# -V6.net
KiCad netlist of a schematic drawn in Altium Designer
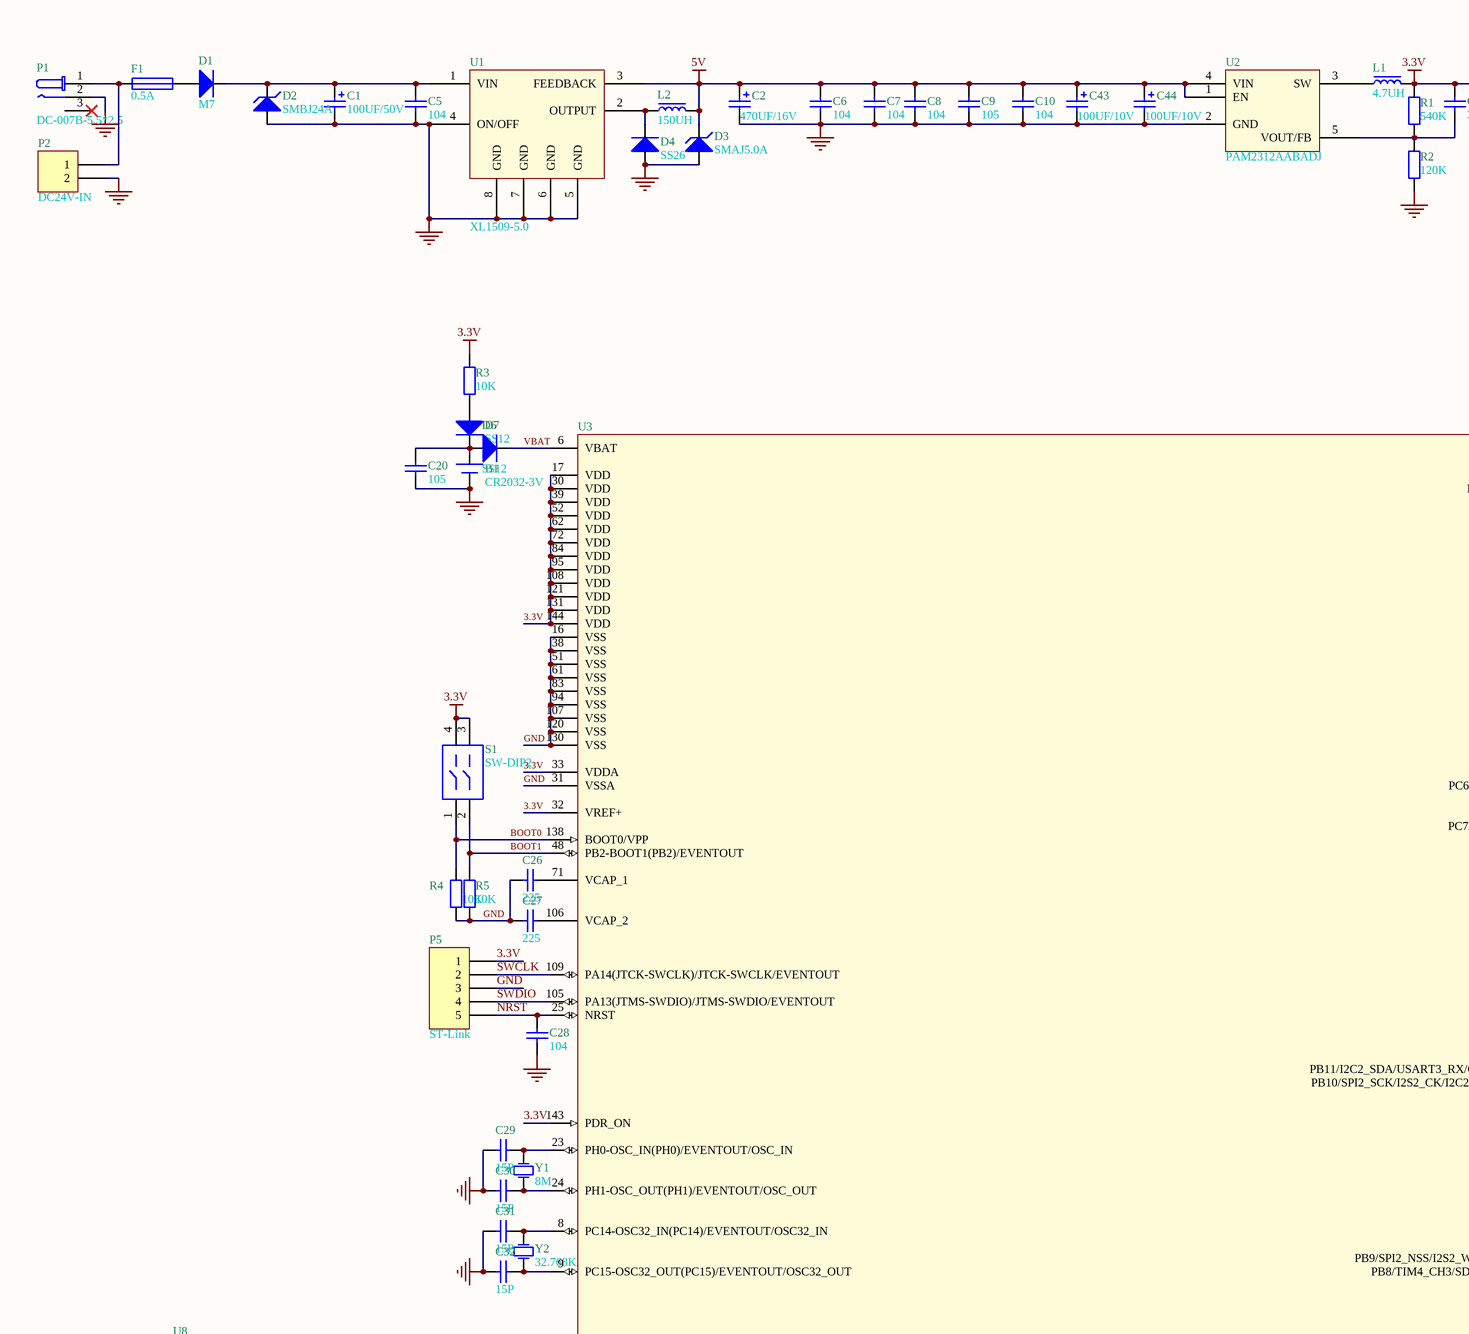
[diagram p0: 通讯转换模块-V6.SchDoc, top left]
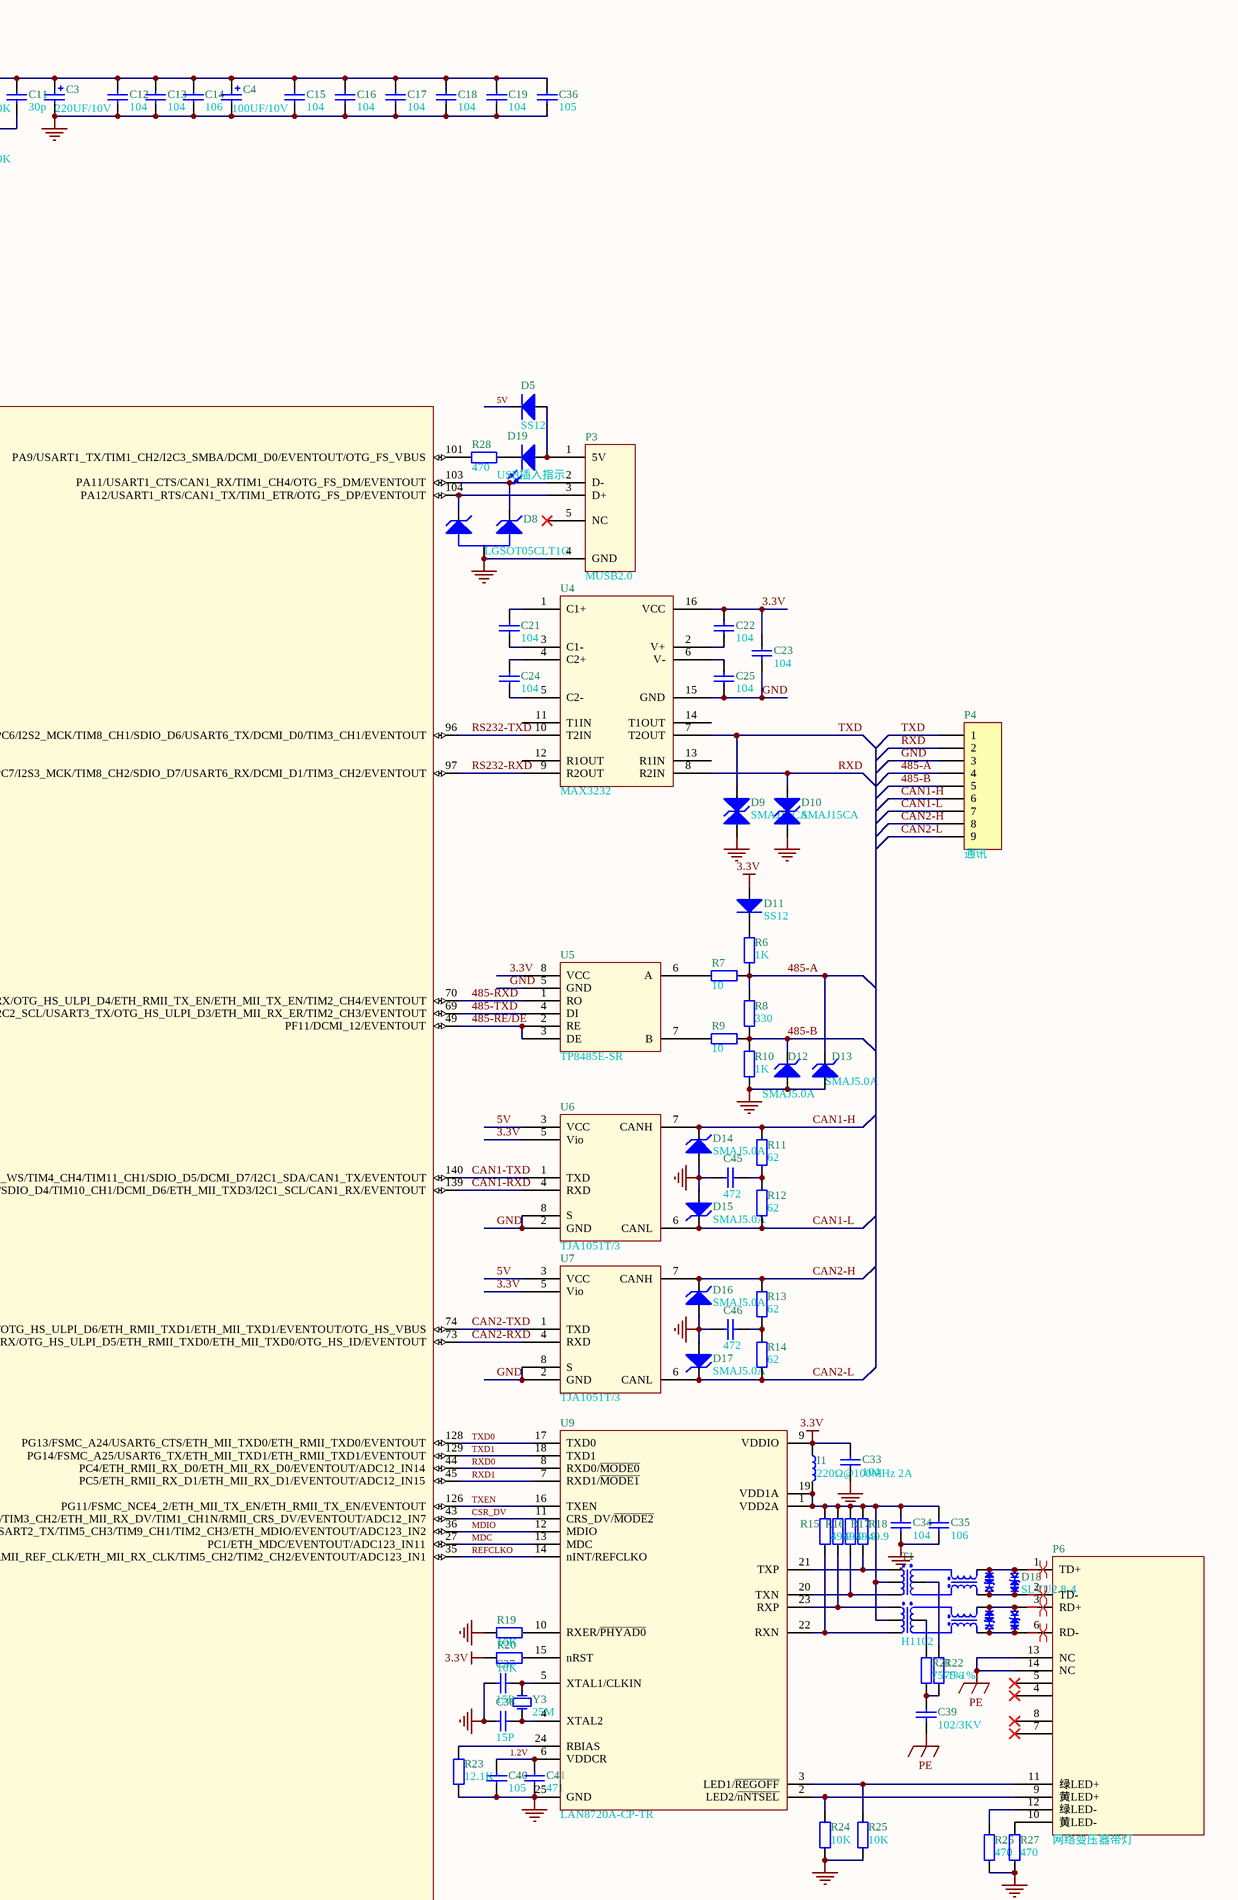
[diagram p1: 通讯转换模块-V6.SchDoc, top right]
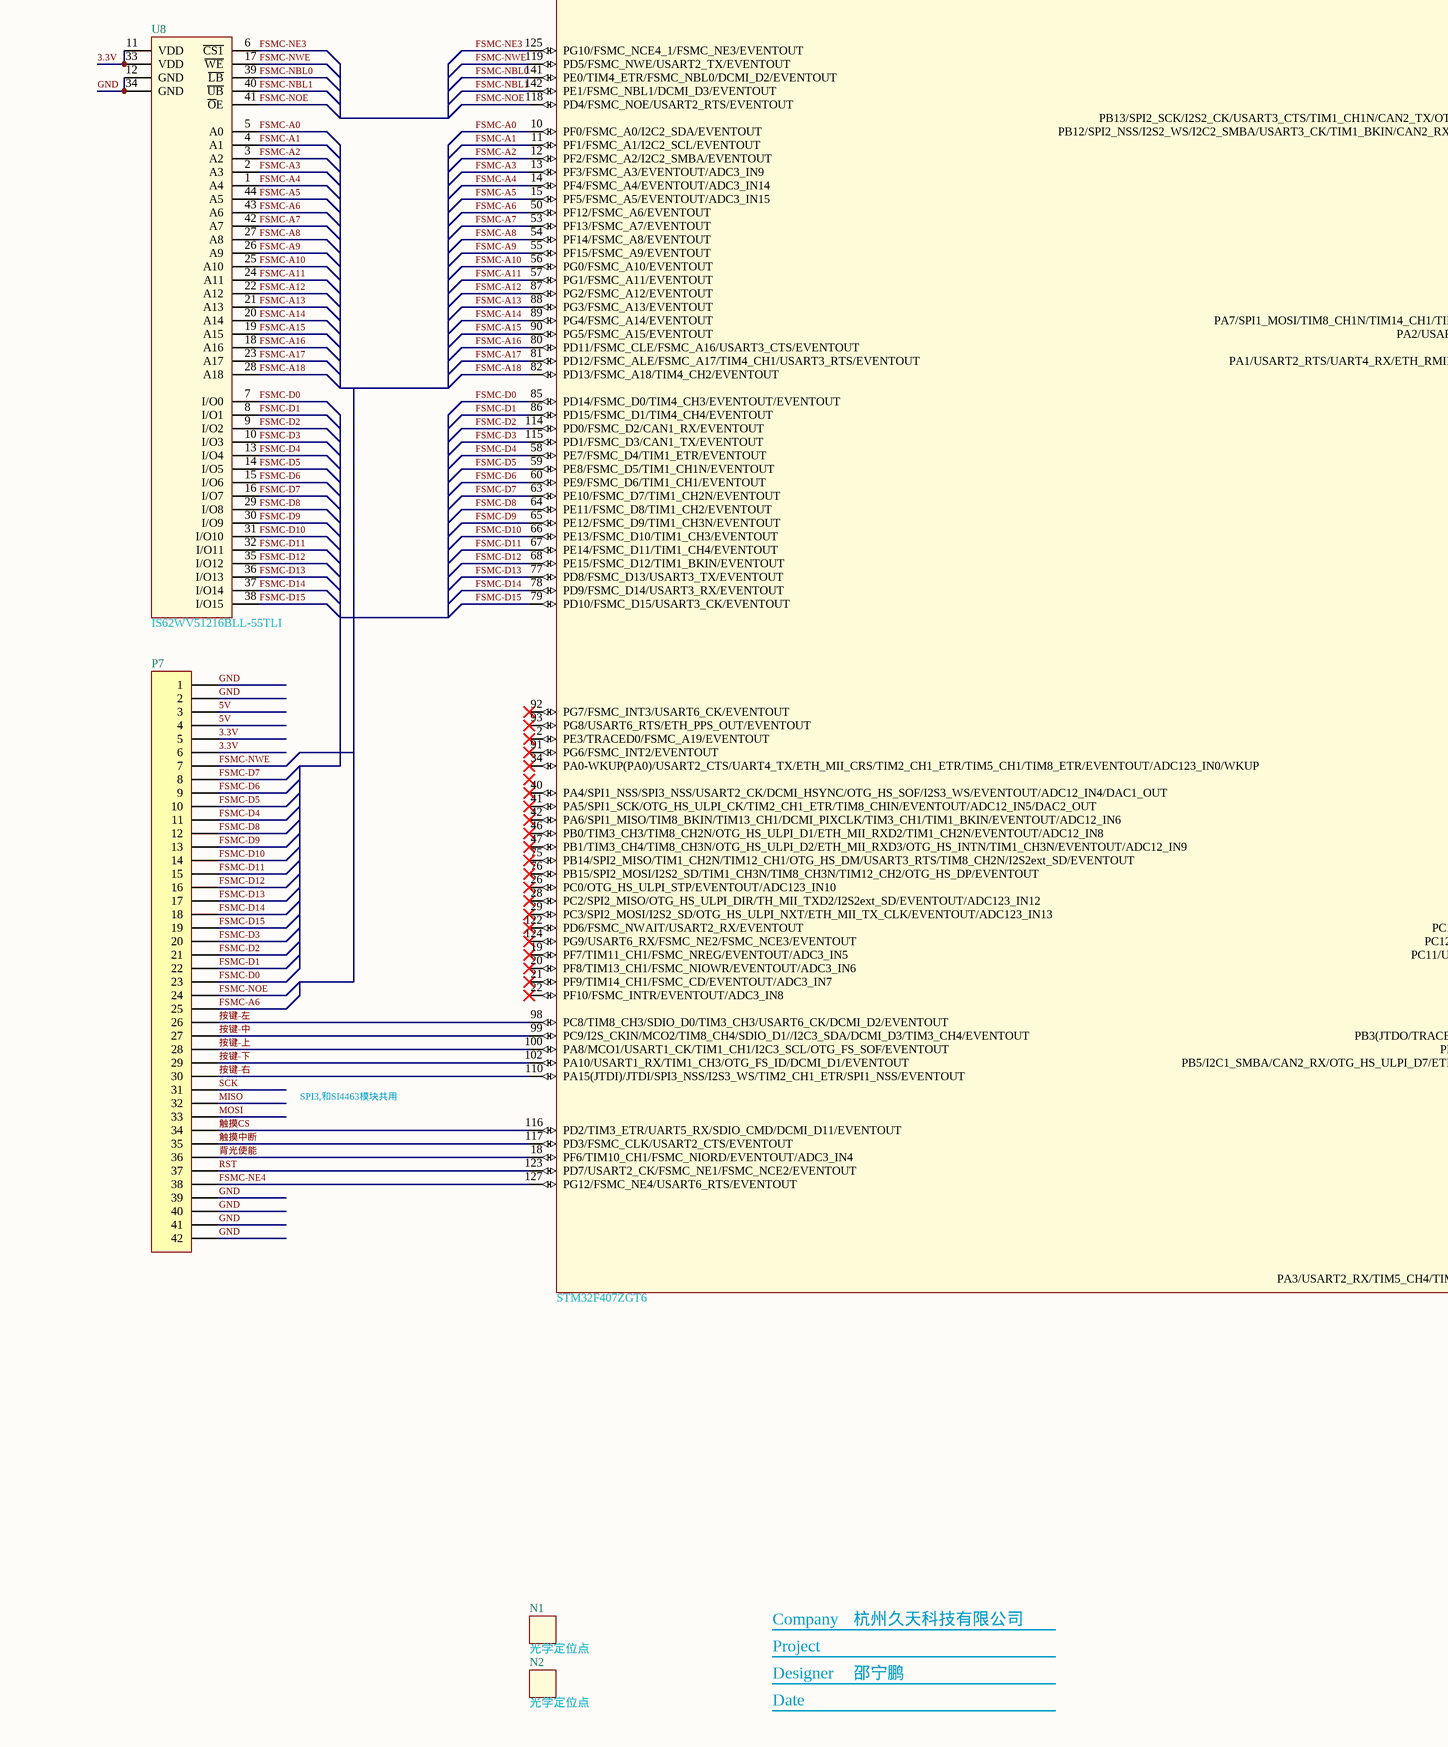
[diagram p2: 通讯转换模块-V6.SchDoc, bottom left]
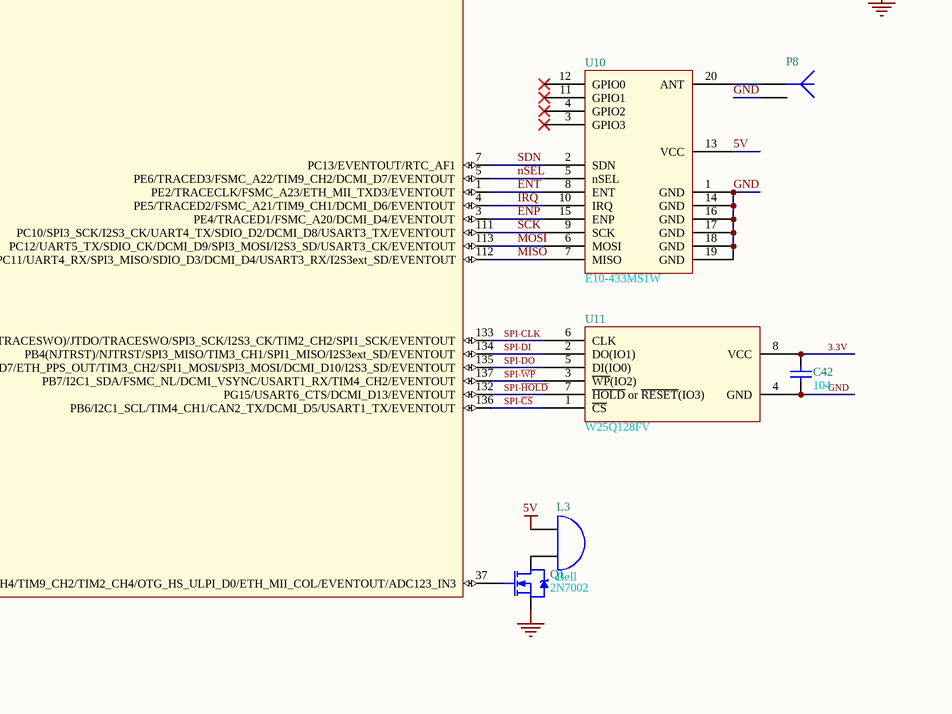
[diagram p3: 通讯转换模块-V6.SchDoc, bottom right]

(export (version "E")
  (design (tool "Eeschema 10.0.6"))
  (components
    (comp (ref "B1")
      (value "CR2032-3V")
      (footprint "CR2032电池座-立式")
      (description "锂电池")
      (libsource (lib "11其他元件-V1.0") (part "Battery1"))
    )
    (comp (ref "C1")
      (value "100UF/50V")
      (footprint "贴片固态电容8*10")
      (description "电解电容")
      (fields (field (name "PUBLISHER") "Altium Limited"))
      (libsource (lib "2电容-V1.0") (part "Cap Pol1"))
    )
    (comp (ref "C2")
      (value "470UF/16V")
      (footprint "贴片固态电容8*10")
      (description "电解电容")
      (fields (field (name "PUBLISHER") "Altium Limited"))
      (libsource (lib "2电容-V1.0") (part "Cap Pol1"))
    )
    (comp (ref "C3")
      (value "220UF/10V")
      (footprint "贴片固态电容6.3*7.7")
      (description "电解电容")
      (fields (field (name "PUBLISHER") "Altium Limited"))
      (libsource (lib "2电容-V1.0") (part "Cap Pol1"))
    )
    (comp (ref "C4")
      (value "100UF/10V")
      (footprint "贴片固态电容5*5.3")
      (description "电解电容")
      (fields (field (name "PUBLISHER") "Altium Limited"))
      (libsource (lib "2电容-V1.0") (part "Cap Pol1"))
    )
    (comp (ref "C5")
      (value "104")
      (footprint "C-0603")
      (description "0805")
      (fields (field (name "PUBLISHER") "Altium Limited"))
      (libsource (lib "2电容-V1.0") (part "Cap-0805"))
    )
    (comp (ref "C6")
      (value "104")
      (footprint "C-0603")
      (description "0805")
      (fields (field (name "PUBLISHER") "Altium Limited"))
      (libsource (lib "2电容-V1.0") (part "Cap-0805"))
    )
    (comp (ref "C7")
      (value "104")
      (footprint "C-0603")
      (description "0805")
      (fields (field (name "PUBLISHER") "Altium Limited"))
      (libsource (lib "2电容-V1.0") (part "Cap-0805"))
    )
    (comp (ref "C8")
      (value "104")
      (footprint "C-0603")
      (description "0805")
      (fields (field (name "PUBLISHER") "Altium Limited"))
      (libsource (lib "2电容-V1.0") (part "Cap-0805"))
    )
    (comp (ref "C9")
      (value "105")
      (footprint "C-0603")
      (description "0805")
      (fields (field (name "PUBLISHER") "Altium Limited"))
      (libsource (lib "2电容-V1.0") (part "Cap-0805"))
    )
    (comp (ref "C10")
      (value "104")
      (footprint "C-0603")
      (description "0805")
      (fields (field (name "PUBLISHER") "Altium Limited"))
      (libsource (lib "2电容-V1.0") (part "Cap-0805"))
    )
    (comp (ref "C11")
      (value "30p")
      (footprint "C-0603")
      (description "0805")
      (fields (field (name "PUBLISHER") "Altium Limited"))
      (libsource (lib "2电容-V1.0") (part "Cap-0805"))
    )
    (comp (ref "C12")
      (value "104")
      (footprint "C-0603")
      (description "0805")
      (fields (field (name "PUBLISHER") "Altium Limited"))
      (libsource (lib "2电容-V1.0") (part "Cap-0805"))
    )
    (comp (ref "C13")
      (value "104")
      (footprint "C-0603")
      (description "0805")
      (fields (field (name "PUBLISHER") "Altium Limited"))
      (libsource (lib "2电容-V1.0") (part "Cap-0805"))
    )
    (comp (ref "C14")
      (value "106")
      (footprint "C-0603")
      (description "0805")
      (fields (field (name "PUBLISHER") "Altium Limited"))
      (libsource (lib "2电容-V1.0") (part "Cap-0805"))
    )
    (comp (ref "C15")
      (value "104")
      (footprint "C-0603")
      (description "0805")
      (fields (field (name "PUBLISHER") "Altium Limited"))
      (libsource (lib "2电容-V1.0") (part "Cap-0805"))
    )
    (comp (ref "C16")
      (value "104")
      (footprint "C-0603")
      (description "0805")
      (fields (field (name "PUBLISHER") "Altium Limited"))
      (libsource (lib "2电容-V1.0") (part "Cap-0805"))
    )
    (comp (ref "C17")
      (value "104")
      (footprint "C-0603")
      (description "0805")
      (fields (field (name "PUBLISHER") "Altium Limited"))
      (libsource (lib "2电容-V1.0") (part "Cap-0805"))
    )
    (comp (ref "C18")
      (value "104")
      (footprint "C-0603")
      (description "0805")
      (fields (field (name "PUBLISHER") "Altium Limited"))
      (libsource (lib "2电容-V1.0") (part "Cap-0805"))
    )
    (comp (ref "C19")
      (value "104")
      (footprint "C-0603")
      (description "0805")
      (fields (field (name "PUBLISHER") "Altium Limited"))
      (libsource (lib "2电容-V1.0") (part "Cap-0805"))
    )
    (comp (ref "C20")
      (value "105")
      (footprint "C-0603")
      (description "0805")
      (fields (field (name "PUBLISHER") "Altium Limited"))
      (libsource (lib "2电容-V1.0") (part "Cap-0603"))
    )
    (comp (ref "C21")
      (value "104")
      (footprint "C-0603")
      (description "0805")
      (fields (field (name "PUBLISHER") "Altium Limited"))
      (libsource (lib "2电容-V1.0") (part "Cap-0805"))
    )
    (comp (ref "C22")
      (value "104")
      (footprint "C-0603")
      (description "0805")
      (fields (field (name "PUBLISHER") "Altium Limited"))
      (libsource (lib "2电容-V1.0") (part "Cap-0805"))
    )
    (comp (ref "C23")
      (value "104")
      (footprint "C-0603")
      (description "0805")
      (fields (field (name "PUBLISHER") "Altium Limited"))
      (libsource (lib "2电容-V1.0") (part "Cap-0805"))
    )
    (comp (ref "C24")
      (value "104")
      (footprint "C-0603")
      (description "0805")
      (fields (field (name "PUBLISHER") "Altium Limited"))
      (libsource (lib "2电容-V1.0") (part "Cap-0805"))
    )
    (comp (ref "C25")
      (value "104")
      (footprint "C-0603")
      (description "0805")
      (fields (field (name "PUBLISHER") "Altium Limited"))
      (libsource (lib "2电容-V1.0") (part "Cap-0805"))
    )
    (comp (ref "C26")
      (value "225")
      (footprint "C-0603")
      (description "0805")
      (fields (field (name "PUBLISHER") "Altium Limited"))
      (libsource (lib "2电容-V1.0") (part "Cap-0603"))
    )
    (comp (ref "C27")
      (value "225")
      (footprint "C-0603")
      (description "0805")
      (fields (field (name "PUBLISHER") "Altium Limited"))
      (libsource (lib "2电容-V1.0") (part "Cap-0603"))
    )
    (comp (ref "C28")
      (value "104")
      (footprint "C-0603")
      (description "0805")
      (fields (field (name "PUBLISHER") "Altium Limited"))
      (libsource (lib "2电容-V1.0") (part "Cap-0603"))
    )
    (comp (ref "C29")
      (value "15P")
      (footprint "C-0603")
      (description "0805")
      (fields (field (name "PUBLISHER") "Altium Limited"))
      (libsource (lib "2电容-V1.0") (part "Cap-0603"))
    )
    (comp (ref "C30")
      (value "15P")
      (footprint "C-0603")
      (description "0805")
      (fields (field (name "PUBLISHER") "Altium Limited"))
      (libsource (lib "2电容-V1.0") (part "Cap-0603"))
    )
    (comp (ref "C31")
      (value "15P")
      (footprint "C-0603")
      (description "0805")
      (fields (field (name "PUBLISHER") "Altium Limited"))
      (libsource (lib "2电容-V1.0") (part "Cap-0603"))
    )
    (comp (ref "C32")
      (value "15P")
      (footprint "C-0603")
      (description "0805")
      (fields (field (name "PUBLISHER") "Altium Limited"))
      (libsource (lib "2电容-V1.0") (part "Cap-0603"))
    )
    (comp (ref "C33")
      (value "104")
      (footprint "C-0603")
      (description "0805")
      (fields (field (name "PUBLISHER") "Altium Limited"))
      (libsource (lib "2电容-V1.0") (part "Cap-0603"))
    )
    (comp (ref "C34")
      (value "104")
      (footprint "C-0603")
      (description "0805")
      (fields (field (name "PUBLISHER") "Altium Limited"))
      (libsource (lib "2电容-V1.0") (part "Cap-0603"))
    )
    (comp (ref "C35")
      (value "106")
      (footprint "C-0603")
      (description "0805")
      (fields (field (name "PUBLISHER") "Altium Limited"))
      (libsource (lib "2电容-V1.0") (part "Cap-0603"))
    )
    (comp (ref "C36")
      (value "105")
      (footprint "C-0603")
      (description "0805")
      (fields (field (name "PUBLISHER") "Altium Limited"))
      (libsource (lib "2电容-V1.0") (part "Cap-0603"))
    )
    (comp (ref "C37")
      (value "15P")
      (footprint "C-0603")
      (description "0805")
      (fields (field (name "PUBLISHER") "Altium Limited"))
      (libsource (lib "2电容-V1.0") (part "Cap-0603"))
    )
    (comp (ref "C38")
      (value "15P")
      (footprint "C-0603")
      (description "0805")
      (fields (field (name "PUBLISHER") "Altium Limited"))
      (libsource (lib "2电容-V1.0") (part "Cap-0603"))
    )
    (comp (ref "C39")
      (value "102/3KV")
      (footprint "C-1206")
      (description "0805")
      (fields (field (name "PUBLISHER") "Altium Limited"))
      (libsource (lib "2电容-V1.0") (part "Cap-0805"))
    )
    (comp (ref "C40")
      (value "105")
      (footprint "C-0603")
      (description "0805")
      (fields (field (name "PUBLISHER") "Altium Limited"))
      (libsource (lib "2电容-V1.0") (part "Cap-0603"))
    )
    (comp (ref "C41")
      (value "471")
      (footprint "C-0603")
      (description "0805")
      (fields (field (name "PUBLISHER") "Altium Limited"))
      (libsource (lib "2电容-V1.0") (part "Cap-0603"))
    )
    (comp (ref "C42")
      (value "104")
      (footprint "C-0603")
      (description "0805")
      (fields (field (name "PUBLISHER") "Altium Limited"))
      (libsource (lib "2电容-V1.0") (part "Cap-0603"))
    )
    (comp (ref "C43")
      (value "100UF/10V")
      (footprint "贴片固态电容5*5.3")
      (description "电解电容")
      (fields (field (name "PUBLISHER") "Altium Limited"))
      (libsource (lib "2电容-V1.0") (part "Cap Pol1"))
    )
    (comp (ref "C44")
      (value "100UF/10V")
      (footprint "贴片固态电容5*5.3")
      (description "电解电容")
      (fields (field (name "PUBLISHER") "Altium Limited"))
      (libsource (lib "2电容-V1.0") (part "Cap Pol1"))
    )
    (comp (ref "C45")
      (value "472")
      (footprint "C-0603")
      (description "0805")
      (fields (field (name "PUBLISHER") "Altium Limited"))
      (libsource (lib "2电容-V1.0") (part "Cap-0603"))
    )
    (comp (ref "C46")
      (value "472")
      (footprint "C-0603")
      (description "0805")
      (fields (field (name "PUBLISHER") "Altium Limited"))
      (libsource (lib "2电容-V1.0") (part "Cap-0603"))
    )
    (comp (ref "D1")
      (value "M7")
      (footprint "SMA")
      (description "SMA")
      (fields (field (name "PUBLISHER") "Altium Limited"))
      (libsource (lib "4二极管-V1.1") (part "M7"))
    )
    (comp (ref "D2")
      (value "SMBJ24A")
      (footprint "SMB")
      (description "SMB")
      (libsource (lib "4二极管-V1.1") (part "TVS-1"))
    )
    (comp (ref "D3")
      (value "SMAJ5.0A")
      (footprint "SMA")
      (description "SMB")
      (libsource (lib "4二极管-V1.1") (part "TVS-1"))
    )
    (comp (ref "D4")
      (value "SS26")
      (footprint "SMA")
      (description "SMA")
      (libsource (lib "4二极管-V1.1") (part "SS14"))
    )
    (comp (ref "D5")
      (value "SS12")
      (footprint "D-1206")
      (description "SMA")
      (libsource (lib "4二极管-V1.1") (part "SS14"))
    )
    (comp (ref "D6")
      (value "SS12")
      (footprint "D-1206")
      (description "SMA")
      (libsource (lib "4二极管-V1.1") (part "SS14"))
    )
    (comp (ref "D7")
      (value "SS12")
      (footprint "D-1206")
      (description "SMA")
      (libsource (lib "4二极管-V1.1") (part "SS14"))
    )
    (comp (ref "D8")
      (value "LGSOT05CLT1G")
      (footprint "SOT-23")
      (description "ESD")
      (libsource (lib "4二极管-V1.1") (part "ESDA5V3L"))
    )
    (comp (ref "D9")
      (value "SMAJ15CA")
      (footprint "SMA无极性")
      (description "SMB")
      (libsource (lib "4二极管-V1.1") (part "TVS-2"))
    )
    (comp (ref "D10")
      (value "SMAJ15CA")
      (footprint "SMA无极性")
      (description "SMB")
      (libsource (lib "4二极管-V1.1") (part "TVS-2"))
    )
    (comp (ref "D11")
      (value "SS12")
      (footprint "D-1206")
      (description "SMA")
      (libsource (lib "4二极管-V1.1") (part "SS14"))
    )
    (comp (ref "D12")
      (value "SMAJ5.0A")
      (footprint "SMA")
      (description "SMB")
      (libsource (lib "4二极管-V1.1") (part "TVS-1"))
    )
    (comp (ref "D13")
      (value "SMAJ5.0A")
      (footprint "SMA")
      (description "SMB")
      (libsource (lib "4二极管-V1.1") (part "TVS-1"))
    )
    (comp (ref "D14")
      (value "SMAJ5.0A")
      (footprint "SMA")
      (description "SMB")
      (libsource (lib "4二极管-V1.1") (part "TVS-1"))
    )
    (comp (ref "D15")
      (value "SMAJ5.0A")
      (footprint "SMA")
      (description "SMB")
      (libsource (lib "4二极管-V1.1") (part "TVS-1"))
    )
    (comp (ref "D16")
      (value "SMAJ5.0A")
      (footprint "SMA")
      (description "SMB")
      (libsource (lib "4二极管-V1.1") (part "TVS-1"))
    )
    (comp (ref "D17")
      (value "SMAJ5.0A")
      (footprint "SMA")
      (description "SMB")
      (libsource (lib "4二极管-V1.1") (part "TVS-1"))
    )
    (comp (ref "D18")
      (value "SLVU2.8-4")
      (footprint "SOP-8-N")
      (libsource (lib "4二极管-V1.1") (part "SLVU2.8-4"))
    )
    (comp (ref "D19")
      (value "USB插入指示")
      (footprint "LED-0603-Red")
      (fields (field (name "PUBLISHER") "Altium Limited"))
      (libsource (lib "4二极管-V1.1") (part "LED-0603-Blue"))
    )
    (comp (ref "F1")
      (value "0.5A")
      (footprint "FUSE-1808")
      (description "Fuse")
      (fields (field (name "PUBLISHER") "Altium Limited"))
      (libsource (lib "11其他元件-V1.0") (part "Fuse 1"))
    )
    (comp (ref "I1")
      (value "220Ω@100MHz 2A")
      (footprint "L-0805")
      (libsource (lib "3电感-V1.0") (part "Inductance1"))
    )
    (comp (ref "L1") (value "4.7UH") (footprint "CD54") (libsource (lib "3电感-V1.0") (part "Inductance3")))
    (comp (ref "L2") (value "150UH") (footprint "CD75") (libsource (lib "3电感-V1.0") (part "Inductance3")))
    (comp (ref "L3")
      (value "Bell")
      (footprint "蜂鸣器 YH-8503-A")
      (description "Electrical Bell")
      (fields (field (name "PUBLISHER") "Altium Limited"))
      (libsource (lib "11其他元件-V1.0") (part "Bell"))
    )
    (comp (ref "N1") (value "光学定位点") (footprint "MARK-1mm-3mm") (libsource (lib "11其他元件-V1.0") (part "无引脚")))
    (comp (ref "N2") (value "光学定位点") (footprint "MARK-1mm-3mm") (libsource (lib "11其他元件-V1.0") (part "无引脚")))
    (comp (ref "P1")
      (value "DC-007B-5.5*2.5")
      (footprint "DC-007B")
      (libsource (lib "PJ系列") (part "DC-007B"))
    )
    (comp (ref "P2")
      (value "DC24V-IN")
      (footprint "KF2EDG5.08V-2P-有挡边-卧式")
      (description "Header, 2-Pin")
      (fields (field (name "PUBLISHER") "Altium Limited"))
      (libsource (lib "5排针-V1.0") (part "Header 2"))
    )
    (comp (ref "P3")
      (value "MUSB2.0")
      (footprint "USB1.1-插件-母座")
      (libsource (lib "11其他元件-V1.0") (part "USB-4_A"))
    )
    (comp (ref "P4")
      (value "通讯")
      (footprint "KF2EDG5.08V-9P-有挡边-卧式")
      (description "Header, 9-Pin")
      (fields (field (name "PUBLISHER") "Altium Limited"))
      (libsource (lib "5排针-V1.0") (part "Header 9"))
    )
    (comp (ref "P5")
      (value "ST-Link")
      (footprint "HDR1X5")
      (description "Header, 5-Pin")
      (fields (field (name "PUBLISHER") "Altium Limited"))
      (libsource (lib "5排针-V1.0") (part "Header 5"))
    )
    (comp (ref "P6")
      (value "网络变压器带灯")
      (footprint "RJ45-8P8C-56带灯")
      (libsource (lib "11其他元件-V1.0") (part "网络变压器带灯"))
    )
    (comp (ref "P7")
      (value "~")
      (footprint "FPC-0.5mm_40P下接翻盖")
      (libsource (lib "5排针-V1.0") (part "MHDR1X42"))
    )
    (comp (ref "P8") (value "SMA-KWE") (footprint "SMA-KWE") (libsource (lib "11其他元件-V1.0") (part "天线座")))
    (comp (ref "Q1") (value "2N7002") (footprint "SOT-23") (libsource (lib "4二极管-V1.1") (part "2N7002")))
    (comp (ref "R1")
      (value "540K")
      (footprint "R-0603")
      (description "0603")
      (fields (field (name "PUBLISHER") "Altium Limited"))
      (libsource (lib "") (part "Res2-0603_1"))
    )
    (comp (ref "R2")
      (value "120K")
      (footprint "R-0603")
      (description "0603")
      (fields (field (name "PUBLISHER") "Altium Limited"))
      (libsource (lib "") (part "Res2-0603_1"))
    )
    (comp (ref "R3")
      (value "10K")
      (footprint "R-0603")
      (description "0603")
      (fields (field (name "PUBLISHER") "Altium Limited"))
      (libsource (lib "") (part "Res2-0603_1"))
    )
    (comp (ref "R4")
      (value "10K")
      (footprint "R-0603")
      (description "0603")
      (fields (field (name "PUBLISHER") "Altium Limited"))
      (libsource (lib "") (part "Res2-0603_1"))
    )
    (comp (ref "R5")
      (value "10K")
      (footprint "R-0603")
      (description "0603")
      (fields (field (name "PUBLISHER") "Altium Limited"))
      (libsource (lib "") (part "Res2-0603_1"))
    )
    (comp (ref "R6")
      (value "1K")
      (footprint "R-0603")
      (description "Resistor")
      (fields (field (name "PUBLISHER") "Altium Limited"))
      (libsource (lib "") (part "Res2_1"))
    )
    (comp (ref "R7")
      (value "10")
      (footprint "R-0805")
      (description "Resistor")
      (fields (field (name "PUBLISHER") "Altium Limited"))
      (libsource (lib "") (part "Res2_1"))
    )
    (comp (ref "R8")
      (value "330")
      (footprint "R-1206")
      (description "Resistor")
      (fields (field (name "PUBLISHER") "Altium Limited"))
      (libsource (lib "Miscellaneous Devices") (part "Res2"))
    )
    (comp (ref "R9")
      (value "10")
      (footprint "R-0805")
      (description "Resistor")
      (fields (field (name "PUBLISHER") "Altium Limited"))
      (libsource (lib "") (part "Res2_1"))
    )
    (comp (ref "R10")
      (value "1K")
      (footprint "R-0603")
      (description "Resistor")
      (fields (field (name "PUBLISHER") "Altium Limited"))
      (libsource (lib "元件2.0") (part "Res2"))
    )
    (comp (ref "R11")
      (value "62")
      (footprint "R-1206")
      (description "Resistor")
      (fields (field (name "PUBLISHER") "Altium Limited"))
      (libsource (lib "Miscellaneous Devices") (part "Res2"))
    )
    (comp (ref "R12")
      (value "62")
      (footprint "R-1206")
      (description "Resistor")
      (fields (field (name "PUBLISHER") "Altium Limited"))
      (libsource (lib "Miscellaneous Devices") (part "Res2"))
    )
    (comp (ref "R13")
      (value "62")
      (footprint "R-1206")
      (description "Resistor")
      (fields (field (name "PUBLISHER") "Altium Limited"))
      (libsource (lib "Miscellaneous Devices") (part "Res2"))
    )
    (comp (ref "R14")
      (value "62")
      (footprint "R-1206")
      (description "Resistor")
      (fields (field (name "PUBLISHER") "Altium Limited"))
      (libsource (lib "Miscellaneous Devices") (part "Res2"))
    )
    (comp (ref "R15")
      (value "49.9")
      (footprint "R-0603")
      (description "Resistor")
      (fields (field (name "PUBLISHER") "Altium Limited"))
      (libsource (lib "元件2.0") (part "Res2"))
    )
    (comp (ref "R16")
      (value "49.9")
      (footprint "R-0603")
      (description "Resistor")
      (fields (field (name "PUBLISHER") "Altium Limited"))
      (libsource (lib "元件2.0") (part "Res2"))
    )
    (comp (ref "R17")
      (value "49.9")
      (footprint "R-0603")
      (description "Resistor")
      (fields (field (name "PUBLISHER") "Altium Limited"))
      (libsource (lib "元件2.0") (part "Res2"))
    )
    (comp (ref "R18")
      (value "49.9")
      (footprint "R-0603")
      (description "Resistor")
      (fields (field (name "PUBLISHER") "Altium Limited"))
      (libsource (lib "元件2.0") (part "Res2"))
    )
    (comp (ref "R19")
      (value "10K")
      (footprint "R-0603")
      (description "0603")
      (fields (field (name "PUBLISHER") "Altium Limited"))
      (libsource (lib "") (part "Res2-0603_2"))
    )
    (comp (ref "R20")
      (value "10K")
      (footprint "R-0603")
      (description "0603")
      (fields (field (name "PUBLISHER") "Altium Limited"))
      (libsource (lib "") (part "Res2-0603_2"))
    )
    (comp (ref "R21")
      (value "75-1%")
      (footprint "R-0603")
      (description "0805")
      (fields (field (name "PUBLISHER") "Altium Limited"))
      (libsource (lib "1电阻-V1.0") (part "Res2-0805"))
    )
    (comp (ref "R22")
      (value "75-1%")
      (footprint "R-0603")
      (description "0805")
      (fields (field (name "PUBLISHER") "Altium Limited"))
      (libsource (lib "") (part "Res2-0805_1"))
    )
    (comp (ref "R23")
      (value "12.1K")
      (footprint "R-0603")
      (description "0603")
      (fields (field (name "PUBLISHER") "Altium Limited"))
      (libsource (lib "1电阻-V1.0") (part "Res2-0603"))
    )
    (comp (ref "R24")
      (value "10K")
      (footprint "R-0603")
      (description "0603")
      (fields (field (name "PUBLISHER") "Altium Limited"))
      (libsource (lib "1电阻-V1.0") (part "Res2-0603"))
    )
    (comp (ref "R25")
      (value "10K")
      (footprint "R-0603")
      (description "0603")
      (fields (field (name "PUBLISHER") "Altium Limited"))
      (libsource (lib "1电阻-V1.0") (part "Res2-0603"))
    )
    (comp (ref "R26")
      (value "470")
      (footprint "R-0603")
      (description "0603")
      (fields (field (name "PUBLISHER") "Altium Limited"))
      (libsource (lib "") (part "Res2-0603_3"))
    )
    (comp (ref "R27")
      (value "470")
      (footprint "R-0603")
      (description "0603")
      (fields (field (name "PUBLISHER") "Altium Limited"))
      (libsource (lib "1电阻-V1.0") (part "Res2-0603"))
    )
    (comp (ref "R28")
      (value "470")
      (footprint "R-0603")
      (description "0603")
      (fields (field (name "PUBLISHER") "Altium Limited"))
      (libsource (lib "") (part "Res2-0603_2"))
    )
    (comp (ref "S1")
      (value "SW-DIP2")
      (footprint "SW-红色拨码开关2P")
      (fields (field (name "PUBLISHER") "Altium Limited"))
      (libsource (lib "开关-V1") (part "SW-DIP2"))
    )
    (comp (ref "T1") (value "H1102") (footprint "H1102") (libsource (lib "3电感-V1.0") (part "H1102")))
    (comp (ref "U1")
      (value "XL1509-5.0")
      (footprint "SOP-8-N")
      (description "开关电源 SOP-8")
      (libsource (lib "8集成电路-V1.1") (part "XL1509-ADJ"))
    )
    (comp (ref "U2")
      (value "PAM2312AABADJ")
      (footprint "SOT-23-5-M")
      (description "开关电源 SOT-23-5")
      (libsource (lib "电源芯片DC-DC") (part "PAM2312"))
    )
    (comp (ref "U3")
      (value "STM32F407ZGT6")
      (footprint "TQFP-144-L")
      (libsource (lib "9单片机-V1.0") (part "STM32F407ZET6"))
    )
    (comp (ref "U4") (value "MAX3232") (footprint "SOP-16-N") (libsource (lib "8集成电路-V1.1") (part "MAX3232")))
    (comp (ref "U5")
      (value "TP8485E-SR")
      (footprint "SOP-8-N")
      (description "RS485总线转串口")
      (libsource (lib "集成电路1.0") (part "MAX3082"))
    )
    (comp (ref "U6") (value "TJA1051T/3") (footprint "SOP-8-N") (libsource (lib "通讯-V1") (part "TJA1051T/3")))
    (comp (ref "U7") (value "TJA1051T/3") (footprint "SOP-8-N") (libsource (lib "通讯-V1") (part "TJA1051T/3")))
    (comp (ref "U8")
      (value "IS62WV51216BLL-55TLI")
      (footprint "TSOP2-44-L")
      (libsource (lib "存储") (part "IS62WV51216BLL-55TLI"))
    )
    (comp (ref "U9")
      (value "LAN8720A-CP-TR")
      (footprint "QFN-24")
      (description "以太网PHY")
      (libsource (lib "通讯-V1") (part "LAN8720A-CP-TR"))
    )
    (comp (ref "U10")
      (value "E10-433MS1W")
      (footprint "E10-433MS1W")
      (description "433模块")
      (libsource (lib "6电路模块-V1.0") (part "E10-433MS1W"))
    )
    (comp (ref "U11")
      (value "W25Q128FV")
      (footprint "SOIC-8-M")
      (description "SPI-FLASH")
      (libsource (lib "8集成电路-V1.1") (part "W25Q128FV"))
    )
    (comp (ref "Y1") (value "8M") (footprint "HC-49SMD") (libsource (lib "11其他元件-V1.0") (part "晶振")))
    (comp (ref "Y2") (value "32.768K") (footprint "FC135") (libsource (lib "11其他元件-V1.0") (part "晶振")))
    (comp (ref "Y3") (value "25M") (footprint "HC-49SMD") (libsource (lib "11其他元件-V1.0") (part "晶振")))
  )
  (nets
    (net (code "1") (name "/1.2V") (class "Default")
      (node (ref "C40") (pin "2") (pinfunction "2_2") (pintype "passive"))
      (node (ref "C41") (pin "2") (pinfunction "2_2") (pintype "passive"))
      (node (ref "U9") (pin "6") (pinfunction "VDDCR_6") (pintype "passive"))
    )
    (net (code "2") (name "/485-A") (class "Default")
      (node (ref "D13") (pin "2") (pinfunction "K_2") (pintype "passive"))
      (node (ref "P4") (pin "4") (pinfunction "4_4") (pintype "passive"))
      (node (ref "R6") (pin "2") (pinfunction "2_2") (pintype "passive"))
      (node (ref "R7") (pin "1") (pinfunction "1_1") (pintype "passive"))
      (node (ref "R8") (pin "1") (pinfunction "1_1") (pintype "passive"))
    )
    (net (code "3") (name "/485-B") (class "Default")
      (node (ref "D12") (pin "2") (pinfunction "K_2") (pintype "passive"))
      (node (ref "P4") (pin "5") (pinfunction "5_5") (pintype "passive"))
      (node (ref "R10") (pin "2") (pinfunction "2_2") (pintype "passive"))
      (node (ref "R8") (pin "2") (pinfunction "2_2") (pintype "passive"))
      (node (ref "R9") (pin "1") (pinfunction "1_1") (pintype "passive"))
    )
    (net (code "4") (name "/485-RE{slash}DE") (class "Default")
      (node (ref "U3") (pin "49") (pinfunction "PF11/DCMI_12/EVENTOUT_49") (pintype "bidirectional"))
      (node (ref "U5") (pin "2") (pinfunction "RE_2") (pintype "passive"))
      (node (ref "U5") (pin "3") (pinfunction "DE_3") (pintype "passive"))
    )
    (net (code "5") (name "/485-RXD") (class "Default")
      (node (ref "U3") (pin "70") (pinfunction "PB11/I2C2_SDA/USART3_RX/OTG_HS_ULPI_D4/ETH_RMII_TX_EN/ETH_MII_TX_EN/TIM2_CH4/EVENTOUT_70") (pintype "bidirectional"))
      (node (ref "U5") (pin "1") (pinfunction "RO_1") (pintype "passive"))
    )
    (net (code "6") (name "/485-TXD") (class "Default")
      (node (ref "U3") (pin "69") (pinfunction "PB10/SPI2_SCK/I2S2_CK/I2C2_SCL/USART3_TX/OTG_HS_ULPI_D3/ETH_MII_RX_ER/TIM2_CH3/EVENTOUT_69") (pintype "bidirectional"))
      (node (ref "U5") (pin "4") (pinfunction "DI_4") (pintype "passive"))
    )
    (net (code "7") (name "/BOOT0") (class "Default")
      (node (ref "R4") (pin "2") (pinfunction "2_2") (pintype "passive"))
      (node (ref "S1") (pin "1") (pinfunction "1_1") (pintype "passive"))
      (node (ref "U3") (pin "138") (pinfunction "BOOT0/VPP_138") (pintype "input"))
    )
    (net (code "8") (name "/BOOT1") (class "Default")
      (node (ref "R5") (pin "2") (pinfunction "2_2") (pintype "passive"))
      (node (ref "S1") (pin "2") (pinfunction "2_2") (pintype "passive"))
      (node (ref "U3") (pin "48") (pinfunction "PB2-BOOT1(PB2)/EVENTOUT_48") (pintype "bidirectional"))
    )
    (net (code "9") (name "/CAN1-H") (class "Default")
      (node (ref "D14") (pin "2") (pinfunction "K_2") (pintype "passive"))
      (node (ref "P4") (pin "6") (pinfunction "6_6") (pintype "passive"))
      (node (ref "R11") (pin "1") (pinfunction "1_1") (pintype "passive"))
      (node (ref "U6") (pin "7") (pinfunction "CANH_7") (pintype "passive"))
    )
    (net (code "10") (name "/CAN1-L") (class "Default")
      (node (ref "D15") (pin "2") (pinfunction "K_2") (pintype "passive"))
      (node (ref "P4") (pin "7") (pinfunction "7_7") (pintype "passive"))
      (node (ref "R12") (pin "2") (pinfunction "2_2") (pintype "passive"))
      (node (ref "U6") (pin "6") (pinfunction "CANL_6") (pintype "passive"))
    )
    (net (code "11") (name "/CAN1-RXD") (class "Default")
      (node (ref "U3") (pin "139") (pinfunction "PB8/TIM4_CH3/SDIO_D4/TIM10_CH1/DCMI_D6/ETH_MII_TXD3/I2C1_SCL/CAN1_RX/EVENTOUT_139") (pintype "bidirectional"))
      (node (ref "U6") (pin "4") (pinfunction "RXD_4") (pintype "passive"))
    )
    (net (code "12") (name "/CAN1-TXD") (class "Default")
      (node (ref "U3") (pin "140") (pinfunction "PB9/SPI2_NSS/I2S2_WS/TIM4_CH4/TIM11_CH1/SDIO_D5/DCMI_D7/I2C1_SDA/CAN1_TX/EVENTOUT_140") (pintype "bidirectional"))
      (node (ref "U6") (pin "1") (pinfunction "TXD_1") (pintype "passive"))
    )
    (net (code "13") (name "/CAN2-H") (class "Default")
      (node (ref "D16") (pin "2") (pinfunction "K_2") (pintype "passive"))
      (node (ref "P4") (pin "8") (pinfunction "8_8") (pintype "passive"))
      (node (ref "R13") (pin "1") (pinfunction "1_1") (pintype "passive"))
      (node (ref "U7") (pin "7") (pinfunction "CANH_7") (pintype "passive"))
    )
    (net (code "14") (name "/CAN2-L") (class "Default")
      (node (ref "D17") (pin "2") (pinfunction "K_2") (pintype "passive"))
      (node (ref "P4") (pin "9") (pinfunction "9_9") (pintype "passive"))
      (node (ref "R14") (pin "2") (pinfunction "2_2") (pintype "passive"))
      (node (ref "U7") (pin "6") (pinfunction "CANL_6") (pintype "passive"))
    )
    (net (code "15") (name "/CAN2-RXD") (class "Default")
      (node (ref "U3") (pin "73") (pinfunction "PB12/SPI2_NSS/I2S2_WS/I2C2_SMBA/USART3_CK/TIM1_BKIN/CAN2_RX/OTG_HS_ULPI_D5/ETH_RMII_TXD0/ETH_MII_TXD0/OTG_HS_ID/EVENTOUT_73") (pintype "bidirectional"))
      (node (ref "U7") (pin "4") (pinfunction "RXD_4") (pintype "passive"))
    )
    (net (code "16") (name "/CAN2-TXD") (class "Default")
      (node (ref "U3") (pin "74") (pinfunction "PB13/SPI2_SCK/I2S2_CK/USART3_CTS/TIM1_CH1N/CAN2_TX/OTG_HS_ULPI_D6/ETH_RMII_TXD1/ETH_MII_TXD1/EVENTOUT/OTG_HS_VBUS_74") (pintype "bidirectional"))
      (node (ref "U7") (pin "1") (pinfunction "TXD_1") (pintype "passive"))
    )
    (net (code "17") (name "/CSR_DV") (class "Default")
      (node (ref "U3") (pin "43") (pinfunction "PA7/SPI1_MOSI/TIM8_CH1N/TIM14_CH1/TIM3_CH2/ETH_MII_RX_DV/TIM1_CH1N/RMII_CRS_DV/EVENTOUT/ADC12_IN7_43") (pintype "bidirectional"))
      (node (ref "U9") (pin "11") (pinfunction "CRS_DV/~{MODE2}_11") (pintype "passive"))
    )
    (net (code "18") (name "/ENP") (class "Default")
      (node (ref "U10") (pin "15") (pinfunction "ENP_15") (pintype "passive"))
      (node (ref "U3") (pin "3") (pinfunction "PE4/TRACED1/FSMC_A20/DCMI_D4/EVENTOUT_3") (pintype "bidirectional"))
    )
    (net (code "19") (name "/ENT") (class "Default")
      (node (ref "U10") (pin "8") (pinfunction "ENT_8") (pintype "passive"))
      (node (ref "U3") (pin "1") (pinfunction "PE2/TRACECLK/FSMC_A23/ETH_MII_TXD3/EVENTOUT_1") (pintype "bidirectional"))
    )
    (net (code "20") (name "/FSMC-A0") (class "Default")
      (node (ref "U3") (pin "10") (pinfunction "PF0/FSMC_A0/I2C2_SDA/EVENTOUT_10") (pintype "bidirectional"))
      (node (ref "U8") (pin "5") (pinfunction "A0_5") (pintype "passive"))
    )
    (net (code "21") (name "/FSMC-A1") (class "Default")
      (node (ref "U3") (pin "11") (pinfunction "PF1/FSMC_A1/I2C2_SCL/EVENTOUT_11") (pintype "bidirectional"))
      (node (ref "U8") (pin "4") (pinfunction "A1_4") (pintype "passive"))
    )
    (net (code "22") (name "/FSMC-A2") (class "Default")
      (node (ref "U3") (pin "12") (pinfunction "PF2/FSMC_A2/I2C2_SMBA/EVENTOUT_12") (pintype "bidirectional"))
      (node (ref "U8") (pin "3") (pinfunction "A2_3") (pintype "passive"))
    )
    (net (code "23") (name "/FSMC-A3") (class "Default")
      (node (ref "U3") (pin "13") (pinfunction "PF3/FSMC_A3/EVENTOUT/ADC3_IN9_13") (pintype "bidirectional"))
      (node (ref "U8") (pin "2") (pinfunction "A3_2") (pintype "passive"))
    )
    (net (code "24") (name "/FSMC-A4") (class "Default")
      (node (ref "U3") (pin "14") (pinfunction "PF4/FSMC_A4/EVENTOUT/ADC3_IN14_14") (pintype "bidirectional"))
      (node (ref "U8") (pin "1") (pinfunction "A4_1") (pintype "passive"))
    )
    (net (code "25") (name "/FSMC-A5") (class "Default")
      (node (ref "U3") (pin "15") (pinfunction "PF5/FSMC_A5/EVENTOUT/ADC3_IN15_15") (pintype "bidirectional"))
      (node (ref "U8") (pin "44") (pinfunction "A5_44") (pintype "passive"))
    )
    (net (code "26") (name "/FSMC-A6") (class "Default")
      (node (ref "P7") (pin "25") (pinfunction "25_25") (pintype "passive"))
      (node (ref "U3") (pin "50") (pinfunction "PF12/FSMC_A6/EVENTOUT_50") (pintype "bidirectional"))
      (node (ref "U8") (pin "43") (pinfunction "A6_43") (pintype "passive"))
    )
    (net (code "27") (name "/FSMC-A7") (class "Default")
      (node (ref "U3") (pin "53") (pinfunction "PF13/FSMC_A7/EVENTOUT_53") (pintype "bidirectional"))
      (node (ref "U8") (pin "42") (pinfunction "A7_42") (pintype "passive"))
    )
    (net (code "28") (name "/FSMC-A8") (class "Default")
      (node (ref "U3") (pin "54") (pinfunction "PF14/FSMC_A8/EVENTOUT_54") (pintype "bidirectional"))
      (node (ref "U8") (pin "27") (pinfunction "A8_27") (pintype "passive"))
    )
    (net (code "29") (name "/FSMC-A9") (class "Default")
      (node (ref "U3") (pin "55") (pinfunction "PF15/FSMC_A9/EVENTOUT_55") (pintype "bidirectional"))
      (node (ref "U8") (pin "26") (pinfunction "A9_26") (pintype "passive"))
    )
    (net (code "30") (name "/FSMC-A10") (class "Default")
      (node (ref "U3") (pin "56") (pinfunction "PG0/FSMC_A10/EVENTOUT_56") (pintype "bidirectional"))
      (node (ref "U8") (pin "25") (pinfunction "A10_25") (pintype "passive"))
    )
    (net (code "31") (name "/FSMC-A11") (class "Default")
      (node (ref "U3") (pin "57") (pinfunction "PG1/FSMC_A11/EVENTOUT_57") (pintype "bidirectional"))
      (node (ref "U8") (pin "24") (pinfunction "A11_24") (pintype "passive"))
    )
    (net (code "32") (name "/FSMC-A12") (class "Default")
      (node (ref "U3") (pin "87") (pinfunction "PG2/FSMC_A12/EVENTOUT_87") (pintype "bidirectional"))
      (node (ref "U8") (pin "22") (pinfunction "A12_22") (pintype "passive"))
    )
    (net (code "33") (name "/FSMC-A13") (class "Default")
      (node (ref "U3") (pin "88") (pinfunction "PG3/FSMC_A13/EVENTOUT_88") (pintype "bidirectional"))
      (node (ref "U8") (pin "21") (pinfunction "A13_21") (pintype "passive"))
    )
    (net (code "34") (name "/FSMC-A14") (class "Default")
      (node (ref "U3") (pin "89") (pinfunction "PG4/FSMC_A14/EVENTOUT_89") (pintype "bidirectional"))
      (node (ref "U8") (pin "20") (pinfunction "A14_20") (pintype "passive"))
    )
    (net (code "35") (name "/FSMC-A15") (class "Default")
      (node (ref "U3") (pin "90") (pinfunction "PG5/FSMC_A15/EVENTOUT_90") (pintype "bidirectional"))
      (node (ref "U8") (pin "19") (pinfunction "A15_19") (pintype "passive"))
    )
    (net (code "36") (name "/FSMC-A16") (class "Default")
      (node (ref "U3") (pin "80") (pinfunction "PD11/FSMC_CLE/FSMC_A16/USART3_CTS/EVENTOUT_80") (pintype "bidirectional"))
      (node (ref "U8") (pin "18") (pinfunction "A16_18") (pintype "passive"))
    )
    (net (code "37") (name "/FSMC-A17") (class "Default")
      (node (ref "U3") (pin "81") (pinfunction "PD12/FSMC_ALE/FSMC_A17/TIM4_CH1/USART3_RTS/EVENTOUT_81") (pintype "bidirectional"))
      (node (ref "U8") (pin "23") (pinfunction "A17_23") (pintype "passive"))
    )
    (net (code "38") (name "/FSMC-A18") (class "Default")
      (node (ref "U3") (pin "82") (pinfunction "PD13/FSMC_A18/TIM4_CH2/EVENTOUT_82") (pintype "bidirectional"))
      (node (ref "U8") (pin "28") (pinfunction "A18_28") (pintype "passive"))
    )
    (net (code "39") (name "/FSMC-D0") (class "Default")
      (node (ref "P7") (pin "23") (pinfunction "23_23") (pintype "passive"))
      (node (ref "U3") (pin "85") (pinfunction "PD14/FSMC_D0/TIM4_CH3/EVENTOUT/EVENTOUT_85") (pintype "bidirectional"))
      (node (ref "U8") (pin "7") (pinfunction "I/O0_7") (pintype "passive"))
    )
    (net (code "40") (name "/FSMC-D1") (class "Default")
      (node (ref "P7") (pin "22") (pinfunction "22_22") (pintype "passive"))
      (node (ref "U3") (pin "86") (pinfunction "PD15/FSMC_D1/TIM4_CH4/EVENTOUT_86") (pintype "bidirectional"))
      (node (ref "U8") (pin "8") (pinfunction "I/O1_8") (pintype "passive"))
    )
    (net (code "41") (name "/FSMC-D2") (class "Default")
      (node (ref "P7") (pin "21") (pinfunction "21_21") (pintype "passive"))
      (node (ref "U3") (pin "114") (pinfunction "PD0/FSMC_D2/CAN1_RX/EVENTOUT_114") (pintype "bidirectional"))
      (node (ref "U8") (pin "9") (pinfunction "I/O2_9") (pintype "passive"))
    )
    (net (code "42") (name "/FSMC-D3") (class "Default")
      (node (ref "P7") (pin "20") (pinfunction "20_20") (pintype "passive"))
      (node (ref "U3") (pin "115") (pinfunction "PD1/FSMC_D3/CAN1_TX/EVENTOUT_115") (pintype "bidirectional"))
      (node (ref "U8") (pin "10") (pinfunction "I/O3_10") (pintype "passive"))
    )
    (net (code "43") (name "/FSMC-D4") (class "Default")
      (node (ref "P7") (pin "11") (pinfunction "11_11") (pintype "passive"))
      (node (ref "U3") (pin "58") (pinfunction "PE7/FSMC_D4/TIM1_ETR/EVENTOUT_58") (pintype "bidirectional"))
      (node (ref "U8") (pin "13") (pinfunction "I/O4_13") (pintype "passive"))
    )
    (net (code "44") (name "/FSMC-D5") (class "Default")
      (node (ref "P7") (pin "10") (pinfunction "10_10") (pintype "passive"))
      (node (ref "U3") (pin "59") (pinfunction "PE8/FSMC_D5/TIM1_CH1N/EVENTOUT_59") (pintype "bidirectional"))
      (node (ref "U8") (pin "14") (pinfunction "I/O5_14") (pintype "passive"))
    )
    (net (code "45") (name "/FSMC-D6") (class "Default")
      (node (ref "P7") (pin "9") (pinfunction "9_9") (pintype "passive"))
      (node (ref "U3") (pin "60") (pinfunction "PE9/FSMC_D6/TIM1_CH1/EVENTOUT_60") (pintype "bidirectional"))
      (node (ref "U8") (pin "15") (pinfunction "I/O6_15") (pintype "passive"))
    )
    (net (code "46") (name "/FSMC-D7") (class "Default")
      (node (ref "P7") (pin "8") (pinfunction "8_8") (pintype "passive"))
      (node (ref "U3") (pin "63") (pinfunction "PE10/FSMC_D7/TIM1_CH2N/EVENTOUT_63") (pintype "bidirectional"))
      (node (ref "U8") (pin "16") (pinfunction "I/O7_16") (pintype "passive"))
    )
    (net (code "47") (name "/FSMC-D8") (class "Default")
      (node (ref "P7") (pin "12") (pinfunction "12_12") (pintype "passive"))
      (node (ref "U3") (pin "64") (pinfunction "PE11/FSMC_D8/TIM1_CH2/EVENTOUT_64") (pintype "bidirectional"))
      (node (ref "U8") (pin "29") (pinfunction "I/O8_29") (pintype "passive"))
    )
    (net (code "48") (name "/FSMC-D9") (class "Default")
      (node (ref "P7") (pin "13") (pinfunction "13_13") (pintype "passive"))
      (node (ref "U3") (pin "65") (pinfunction "PE12/FSMC_D9/TIM1_CH3N/EVENTOUT_65") (pintype "bidirectional"))
      (node (ref "U8") (pin "30") (pinfunction "I/O9_30") (pintype "passive"))
    )
    (net (code "49") (name "/FSMC-D10") (class "Default")
      (node (ref "P7") (pin "14") (pinfunction "14_14") (pintype "passive"))
      (node (ref "U3") (pin "66") (pinfunction "PE13/FSMC_D10/TIM1_CH3/EVENTOUT_66") (pintype "bidirectional"))
      (node (ref "U8") (pin "31") (pinfunction "I/O10_31") (pintype "passive"))
    )
    (net (code "50") (name "/FSMC-D11") (class "Default")
      (node (ref "P7") (pin "15") (pinfunction "15_15") (pintype "passive"))
      (node (ref "U3") (pin "67") (pinfunction "PE14/FSMC_D11/TIM1_CH4/EVENTOUT_67") (pintype "bidirectional"))
      (node (ref "U8") (pin "32") (pinfunction "I/O11_32") (pintype "passive"))
    )
    (net (code "51") (name "/FSMC-D12") (class "Default")
      (node (ref "P7") (pin "16") (pinfunction "16_16") (pintype "passive"))
      (node (ref "U3") (pin "68") (pinfunction "PE15/FSMC_D12/TIM1_BKIN/EVENTOUT_68") (pintype "bidirectional"))
      (node (ref "U8") (pin "35") (pinfunction "I/O12_35") (pintype "passive"))
    )
    (net (code "52") (name "/FSMC-D13") (class "Default")
      (node (ref "P7") (pin "17") (pinfunction "17_17") (pintype "passive"))
      (node (ref "U3") (pin "77") (pinfunction "PD8/FSMC_D13/USART3_TX/EVENTOUT_77") (pintype "bidirectional"))
      (node (ref "U8") (pin "36") (pinfunction "I/O13_36") (pintype "passive"))
    )
    (net (code "53") (name "/FSMC-D14") (class "Default")
      (node (ref "P7") (pin "18") (pinfunction "18_18") (pintype "passive"))
      (node (ref "U3") (pin "78") (pinfunction "PD9/FSMC_D14/USART3_RX/EVENTOUT_78") (pintype "bidirectional"))
      (node (ref "U8") (pin "37") (pinfunction "I/O14_37") (pintype "passive"))
    )
    (net (code "54") (name "/FSMC-D15") (class "Default")
      (node (ref "P7") (pin "19") (pinfunction "19_19") (pintype "passive"))
      (node (ref "U3") (pin "79") (pinfunction "PD10/FSMC_D15/USART3_CK/EVENTOUT_79") (pintype "bidirectional"))
      (node (ref "U8") (pin "38") (pinfunction "I/O15_38") (pintype "passive"))
    )
    (net (code "55") (name "/FSMC-NBL0") (class "Default")
      (node (ref "U3") (pin "141") (pinfunction "PE0/TIM4_ETR/FSMC_NBL0/DCMI_D2/EVENTOUT_141") (pintype "bidirectional"))
      (node (ref "U8") (pin "39") (pinfunction "~{LB}_39") (pintype "passive"))
    )
    (net (code "56") (name "/FSMC-NBL1") (class "Default")
      (node (ref "U3") (pin "142") (pinfunction "PE1/FSMC_NBL1/DCMI_D3/EVENTOUT_142") (pintype "bidirectional"))
      (node (ref "U8") (pin "40") (pinfunction "~{UB}_40") (pintype "passive"))
    )
    (net (code "57") (name "/FSMC-NE3") (class "Default")
      (node (ref "U3") (pin "125") (pinfunction "PG10/FSMC_NCE4_1/FSMC_NE3/EVENTOUT_125") (pintype "bidirectional"))
      (node (ref "U8") (pin "6") (pinfunction "~{CS1}_6") (pintype "passive"))
    )
    (net (code "58") (name "/FSMC-NE4") (class "Default")
      (node (ref "P7") (pin "38") (pinfunction "38_38") (pintype "passive"))
      (node (ref "U3") (pin "127") (pinfunction "PG12/FSMC_NE4/USART6_RTS/EVENTOUT_127") (pintype "bidirectional"))
    )
    (net (code "59") (name "/FSMC-NOE") (class "Default")
      (node (ref "P7") (pin "24") (pinfunction "24_24") (pintype "passive"))
      (node (ref "U3") (pin "118") (pinfunction "PD4/FSMC_NOE/USART2_RTS/EVENTOUT_118") (pintype "bidirectional"))
      (node (ref "U8") (pin "41") (pinfunction "~{O}E_41") (pintype "passive"))
    )
    (net (code "60") (name "/FSMC-NWE") (class "Default")
      (node (ref "P7") (pin "7") (pinfunction "7_7") (pintype "passive"))
      (node (ref "U3") (pin "119") (pinfunction "PD5/FSMC_NWE/USART2_TX/EVENTOUT_119") (pintype "bidirectional"))
      (node (ref "U8") (pin "17") (pinfunction "~{WE}_17") (pintype "passive"))
    )
    (net (code "61") (name "/IRQ") (class "Default")
      (node (ref "U10") (pin "10") (pinfunction "IRQ_10") (pintype "passive"))
      (node (ref "U3") (pin "4") (pinfunction "PE5/TRACED2/FSMC_A21/TIM9_CH1/DCMI_D6/EVENTOUT_4") (pintype "bidirectional"))
    )
    (net (code "62") (name "/MDC") (class "Default")
      (node (ref "U3") (pin "27") (pinfunction "PC1/ETH_MDC/EVENTOUT/ADC123_IN11_27") (pintype "bidirectional"))
      (node (ref "U9") (pin "13") (pinfunction "MDC_13") (pintype "passive"))
    )
    (net (code "63") (name "/MDIO") (class "Default")
      (node (ref "U3") (pin "36") (pinfunction "PA2/USART2_TX/TIM5_CH3/TIM9_CH1/TIM2_CH3/ETH_MDIO/EVENTOUT/ADC123_IN2_36") (pintype "bidirectional"))
      (node (ref "U9") (pin "12") (pinfunction "MDIO_12") (pintype "passive"))
    )
    (net (code "64") (name "/MISO") (class "Default")
      (node (ref "P7") (pin "32") (pinfunction "32_32") (pintype "passive"))
      (node (ref "U10") (pin "7") (pinfunction "MISO_7") (pintype "passive"))
      (node (ref "U3") (pin "112") (pinfunction "PC11/UART4_RX/SPI3_MISO/SDIO_D3/DCMI_D4/USART3_RX/I2S3ext_SD/EVENTOUT_112") (pintype "bidirectional"))
    )
    (net (code "65") (name "/MOSI") (class "Default")
      (node (ref "P7") (pin "33") (pinfunction "33_33") (pintype "passive"))
      (node (ref "U10") (pin "6") (pinfunction "MOSI_6") (pintype "passive"))
      (node (ref "U3") (pin "113") (pinfunction "PC12/UART5_TX/SDIO_CK/DCMI_D9/SPI3_MOSI/I2S3_SD/USART3_CK/EVENTOUT_113") (pintype "bidirectional"))
    )
    (net (code "66") (name "/NRST") (class "Default")
      (node (ref "C28") (pin "2") (pinfunction "2_2") (pintype "passive"))
      (node (ref "P5") (pin "5") (pinfunction "5_5") (pintype "passive"))
      (node (ref "U3") (pin "25") (pinfunction "NRST_25") (pintype "bidirectional"))
    )
    (net (code "67") (name "/REFCLKO") (class "Default")
      (node (ref "U3") (pin "35") (pinfunction "PA1/USART2_RTS/UART4_RX/ETH_RMII_REF_CLK/ETH_MII_RX_CLK/TIM5_CH2/TIM2_CH2/EVENTOUT/ADC123_IN1_35") (pintype "bidirectional"))
      (node (ref "U9") (pin "14") (pinfunction "nINT/REFCLKO_14") (pintype "passive"))
    )
    (net (code "68") (name "/RS232-RXD") (class "Default")
      (node (ref "U3") (pin "97") (pinfunction "PC7/I2S3_MCK/TIM8_CH2/SDIO_D7/USART6_RX/DCMI_D1/TIM3_CH2/EVENTOUT_97") (pintype "bidirectional"))
      (node (ref "U4") (pin "9") (pinfunction "R2OUT_9") (pintype "passive"))
    )
    (net (code "69") (name "/RS232-TXD") (class "Default")
      (node (ref "U3") (pin "96") (pinfunction "PC6/I2S2_MCK/TIM8_CH1/SDIO_D6/USART6_TX/DCMI_D0/TIM3_CH1/EVENTOUT_96") (pintype "bidirectional"))
      (node (ref "U4") (pin "10") (pinfunction "T2IN_10") (pintype "passive"))
    )
    (net (code "70") (name "/RST") (class "Default")
      (node (ref "P7") (pin "37") (pinfunction "37_37") (pintype "passive"))
      (node (ref "U3") (pin "123") (pinfunction "PD7/USART2_CK/FSMC_NE1/FSMC_NCE2/EVENTOUT_123") (pintype "bidirectional"))
    )
    (net (code "71") (name "/RXD") (class "Default")
      (node (ref "D10") (pin "2") (pinfunction "K_2") (pintype "passive"))
      (node (ref "P4") (pin "2") (pinfunction "2_2") (pintype "passive"))
      (node (ref "U4") (pin "8") (pinfunction "R2IN_8") (pintype "passive"))
    )
    (net (code "72") (name "/RXD0") (class "Default")
      (node (ref "U3") (pin "44") (pinfunction "PC4/ETH_RMII_RX_D0/ETH_MII_RX_D0/EVENTOUT/ADC12_IN14_44") (pintype "bidirectional"))
      (node (ref "U9") (pin "8") (pinfunction "RXD0/~{MODE0}_8") (pintype "passive"))
    )
    (net (code "73") (name "/RXD1") (class "Default")
      (node (ref "U3") (pin "45") (pinfunction "PC5/ETH_RMII_RX_D1/ETH_MII_RX_D1/EVENTOUT/ADC12_IN15_45") (pintype "bidirectional"))
      (node (ref "U9") (pin "7") (pinfunction "RXD1/~{MODE1}_7") (pintype "passive"))
    )
    (net (code "74") (name "/SCK") (class "Default")
      (node (ref "P7") (pin "31") (pinfunction "31_31") (pintype "passive"))
      (node (ref "U10") (pin "9") (pinfunction "SCK_9") (pintype "passive"))
      (node (ref "U3") (pin "111") (pinfunction "PC10/SPI3_SCK/I2S3_CK/UART4_TX/SDIO_D2/DCMI_D8/USART3_TX/EVENTOUT_111") (pintype "bidirectional"))
    )
    (net (code "75") (name "/SDN") (class "Default")
      (node (ref "U10") (pin "2") (pinfunction "SDN_2") (pintype "passive"))
      (node (ref "U3") (pin "7") (pinfunction "PC13/EVENTOUT/RTC_AF1_7") (pintype "bidirectional"))
    )
    (net (code "76") (name "/SPI-CLK") (class "Default")
      (node (ref "U11") (pin "6") (pinfunction "CLK_6") (pintype "passive"))
      (node (ref "U3") (pin "133") (pinfunction "PB3(JTDO/TRACESWO)/JTDO/TRACESWO/SPI3_SCK/I2S3_CK/TIM2_CH2/SPI1_SCK/EVENTOUT_133") (pintype "bidirectional"))
    )
    (net (code "77") (name "/SPI-DI") (class "Default")
      (node (ref "U11") (pin "2") (pinfunction "DO(IO1)_2") (pintype "passive"))
      (node (ref "U3") (pin "134") (pinfunction "PB4(NJTRST)/NJTRST/SPI3_MISO/TIM3_CH1/SPI1_MISO/I2S3ext_SD/EVENTOUT_134") (pintype "bidirectional"))
    )
    (net (code "78") (name "/SPI-DO") (class "Default")
      (node (ref "U11") (pin "5") (pinfunction "DI(IO0)_5") (pintype "passive"))
      (node (ref "U3") (pin "135") (pinfunction "PB5/I2C1_SMBA/CAN2_RX/OTG_HS_ULPI_D7/ETH_PPS_OUT/TIM3_CH2/SPI1_MOSI/SPI3_MOSI/DCMI_D10/I2S3_SD/EVENTOUT_135") (pintype "bidirectional"))
    )
    (net (code "79") (name "/SPI-~{CS}") (class "Default")
      (node (ref "U11") (pin "1") (pinfunction "~{CS}_1") (pintype "passive"))
      (node (ref "U3") (pin "136") (pinfunction "PB6/I2C1_SCL/TIM4_CH1/CAN2_TX/DCMI_D5/USART1_TX/EVENTOUT_136") (pintype "bidirectional"))
    )
    (net (code "80") (name "/SPI-~{HOLD}") (class "Default")
      (node (ref "U11") (pin "7") (pinfunction "~{HOLD}_or_~{RESET}(IO3)_7") (pintype "passive"))
      (node (ref "U3") (pin "132") (pinfunction "PG15/USART6_CTS/DCMI_D13/EVENTOUT_132") (pintype "bidirectional"))
    )
    (net (code "81") (name "/SPI-~{WP}") (class "Default")
      (node (ref "U11") (pin "3") (pinfunction "~{WP}(IO2)_3") (pintype "passive"))
      (node (ref "U3") (pin "137") (pinfunction "PB7/I2C1_SDA/FSMC_NL/DCMI_VSYNC/USART1_RX/TIM4_CH2/EVENTOUT_137") (pintype "bidirectional"))
    )
    (net (code "82") (name "/SWCLK") (class "Default")
      (node (ref "P5") (pin "2") (pinfunction "2_2") (pintype "passive"))
      (node (ref "U3") (pin "109") (pinfunction "PA14(JTCK-SWCLK)/JTCK-SWCLK/EVENTOUT_109") (pintype "bidirectional"))
    )
    (net (code "83") (name "/SWDIO") (class "Default")
      (node (ref "P5") (pin "4") (pinfunction "4_4") (pintype "passive"))
      (node (ref "U3") (pin "105") (pinfunction "PA13(JTMS-SWDIO)/JTMS-SWDIO/EVENTOUT_105") (pintype "bidirectional"))
    )
    (net (code "84") (name "/TXD") (class "Default")
      (node (ref "D9") (pin "2") (pinfunction "K_2") (pintype "passive"))
      (node (ref "P4") (pin "1") (pinfunction "1_1") (pintype "passive"))
      (node (ref "U4") (pin "7") (pinfunction "T2OUT_7") (pintype "passive"))
    )
    (net (code "85") (name "/TXD0") (class "Default")
      (node (ref "U3") (pin "128") (pinfunction "PG13/FSMC_A24/USART6_CTS/ETH_MII_TXD0/ETH_RMII_TXD0/EVENTOUT_128") (pintype "bidirectional"))
      (node (ref "U9") (pin "17") (pinfunction "TXD0_17") (pintype "passive"))
    )
    (net (code "86") (name "/TXD1") (class "Default")
      (node (ref "U3") (pin "129") (pinfunction "PG14/FSMC_A25/USART6_TX/ETH_MII_TXD1/ETH_RMII_TXD1/EVENTOUT_129") (pintype "bidirectional"))
      (node (ref "U9") (pin "18") (pinfunction "TXD1_18") (pintype "passive"))
    )
    (net (code "87") (name "/TXEN") (class "Default")
      (node (ref "U3") (pin "126") (pinfunction "PG11/FSMC_NCE4_2/ETH_MII_TX_EN/ETH_RMII_TX_EN/EVENTOUT_126") (pintype "bidirectional"))
      (node (ref "U9") (pin "16") (pinfunction "TXEN_16") (pintype "passive"))
    )
    (net (code "88") (name "/VBAT") (class "Default")
      (node (ref "D6") (pin "2") (pinfunction "K_2") (pintype "passive"))
      (node (ref "U3") (pin "6") (pinfunction "VBAT_6") (pintype "power_in"))
    )
    (net (code "89") (name "/nSEL") (class "Default")
      (node (ref "U10") (pin "5") (pinfunction "nSEL_5") (pintype "passive"))
      (node (ref "U3") (pin "5") (pinfunction "PE6/TRACED3/FSMC_A22/TIM9_CH2/DCMI_D7/EVENTOUT_5") (pintype "bidirectional"))
    )
    (net (code "90") (name "/按键-上") (class "Default")
      (node (ref "P7") (pin "28") (pinfunction "28_28") (pintype "passive"))
      (node (ref "U3") (pin "100") (pinfunction "PA8/MCO1/USART1_CK/TIM1_CH1/I2C3_SCL/OTG_FS_SOF/EVENTOUT_100") (pintype "bidirectional"))
    )
    (net (code "91") (name "/按键-下") (class "Default")
      (node (ref "P7") (pin "29") (pinfunction "29_29") (pintype "passive"))
      (node (ref "U3") (pin "102") (pinfunction "PA10/USART1_RX/TIM1_CH3/OTG_FS_ID/DCMI_D1/EVENTOUT_102") (pintype "bidirectional"))
    )
    (net (code "92") (name "/按键-中") (class "Default")
      (node (ref "P7") (pin "27") (pinfunction "27_27") (pintype "passive"))
      (node (ref "U3") (pin "99") (pinfunction "PC9/I2S_CKIN/MCO2/TIM8_CH4/SDIO_D1//I2C3_SDA/DCMI_D3/TIM3_CH4/EVENTOUT_99") (pintype "bidirectional"))
    )
    (net (code "93") (name "/按键-右") (class "Default")
      (node (ref "P7") (pin "30") (pinfunction "30_30") (pintype "passive"))
      (node (ref "U3") (pin "110") (pinfunction "PA15(JTDI)/JTDI/SPI3_NSS/I2S3_WS/TIM2_CH1_ETR/SPI1_NSS/EVENTOUT_110") (pintype "bidirectional"))
    )
    (net (code "94") (name "/按键-左") (class "Default")
      (node (ref "P7") (pin "26") (pinfunction "26_26") (pintype "passive"))
      (node (ref "U3") (pin "98") (pinfunction "PC8/TIM8_CH3/SDIO_D0/TIM3_CH3/USART6_CK/DCMI_D2/EVENTOUT_98") (pintype "bidirectional"))
    )
    (net (code "95") (name "/背光使能") (class "Default")
      (node (ref "P7") (pin "36") (pinfunction "36_36") (pintype "passive"))
      (node (ref "U3") (pin "18") (pinfunction "PF6/TIM10_CH1/FSMC_NIORD/EVENTOUT/ADC3_IN4_18") (pintype "bidirectional"))
    )
    (net (code "96") (name "/触摸CS") (class "Default")
      (node (ref "P7") (pin "34") (pinfunction "34_34") (pintype "passive"))
      (node (ref "U3") (pin "116") (pinfunction "PD2/TIM3_ETR/UART5_RX/SDIO_CMD/DCMI_D11/EVENTOUT_116") (pintype "bidirectional"))
    )
    (net (code "97") (name "/触摸中断") (class "Default")
      (node (ref "P7") (pin "35") (pinfunction "35_35") (pintype "passive"))
      (node (ref "U3") (pin "117") (pinfunction "PD3/FSMC_CLK/USART2_CTS/EVENTOUT_117") (pintype "bidirectional"))
    )
    (net (code "98") (name "3.3V") (class "Default")
      (node (ref "C11") (pin "2") (pinfunction "2_2") (pintype "passive"))
      (node (ref "C12") (pin "2") (pinfunction "2_2") (pintype "passive"))
      (node (ref "C13") (pin "2") (pinfunction "2_2") (pintype "passive"))
      (node (ref "C14") (pin "2") (pinfunction "2_2") (pintype "passive"))
      (node (ref "C15") (pin "2") (pinfunction "2_2") (pintype "passive"))
      (node (ref "C16") (pin "2") (pinfunction "2_2") (pintype "passive"))
      (node (ref "C17") (pin "2") (pinfunction "2_2") (pintype "passive"))
      (node (ref "C18") (pin "2") (pinfunction "2_2") (pintype "passive"))
      (node (ref "C19") (pin "2") (pinfunction "2_2") (pintype "passive"))
      (node (ref "C22") (pin "2") (pinfunction "2_2") (pintype "passive"))
      (node (ref "C23") (pin "2") (pinfunction "2_2") (pintype "passive"))
      (node (ref "C3") (pin "1") (pinfunction "1_1") (pintype "passive"))
      (node (ref "C33") (pin "2") (pinfunction "2_2") (pintype "passive"))
      (node (ref "C36") (pin "2") (pinfunction "2_2") (pintype "passive"))
      (node (ref "C4") (pin "1") (pinfunction "1_1") (pintype "passive"))
      (node (ref "C42") (pin "2") (pinfunction "2_2") (pintype "passive"))
      (node (ref "D11") (pin "1") (pinfunction "A_1") (pintype "passive"))
      (node (ref "I1") (pin "2") (pinfunction "2_2") (pintype "passive"))
      (node (ref "L1") (pin "2") (pinfunction "2_2") (pintype "passive"))
      (node (ref "P5") (pin "1") (pinfunction "1_1") (pintype "passive"))
      (node (ref "P7") (pin "5") (pinfunction "5_5") (pintype "passive"))
      (node (ref "P7") (pin "6") (pinfunction "6_6") (pintype "passive"))
      (node (ref "R1") (pin "2") (pinfunction "2_2") (pintype "passive"))
      (node (ref "R20") (pin "2") (pinfunction "2_2") (pintype "passive"))
      (node (ref "R3") (pin "2") (pinfunction "2_2") (pintype "passive"))
      (node (ref "S1") (pin "3") (pinfunction "3_3") (pintype "passive"))
      (node (ref "S1") (pin "4") (pinfunction "4_4") (pintype "passive"))
      (node (ref "U11") (pin "8") (pinfunction "VCC_8") (pintype "passive"))
      (node (ref "U3") (pin "108") (pinfunction "VDD_108") (pintype "power_in"))
      (node (ref "U3") (pin "121") (pinfunction "VDD_121") (pintype "power_in"))
      (node (ref "U3") (pin "131") (pinfunction "VDD_131") (pintype "power_in"))
      (node (ref "U3") (pin "143") (pinfunction "PDR_ON_143") (pintype "input"))
      (node (ref "U3") (pin "144") (pinfunction "VDD_144") (pintype "power_in"))
      (node (ref "U3") (pin "17") (pinfunction "VDD_17") (pintype "power_in"))
      (node (ref "U3") (pin "30") (pinfunction "VDD_30") (pintype "power_in"))
      (node (ref "U3") (pin "32") (pinfunction "VREF+_32") (pintype "power_in"))
      (node (ref "U3") (pin "33") (pinfunction "VDDA_33") (pintype "power_in"))
      (node (ref "U3") (pin "39") (pinfunction "VDD_39") (pintype "power_in"))
      (node (ref "U3") (pin "52") (pinfunction "VDD_52") (pintype "power_in"))
      (node (ref "U3") (pin "62") (pinfunction "VDD_62") (pintype "power_in"))
      (node (ref "U3") (pin "72") (pinfunction "VDD_72") (pintype "power_in"))
      (node (ref "U3") (pin "84") (pinfunction "VDD_84") (pintype "power_in"))
      (node (ref "U3") (pin "95") (pinfunction "VDD_95") (pintype "power_in"))
      (node (ref "U4") (pin "16") (pinfunction "VCC_16") (pintype "passive"))
      (node (ref "U5") (pin "8") (pinfunction "VCC_8") (pintype "passive"))
      (node (ref "U6") (pin "5") (pinfunction "Vio_5") (pintype "passive"))
      (node (ref "U7") (pin "5") (pinfunction "Vio_5") (pintype "passive"))
      (node (ref "U8") (pin "11") (pinfunction "VDD_11") (pintype "passive"))
      (node (ref "U8") (pin "33") (pinfunction "VDD_33") (pintype "passive"))
      (node (ref "U9") (pin "9") (pinfunction "VDDIO_9") (pintype "passive"))
    )
    (net (code "99") (name "5V") (class "Default")
      (node (ref "C10") (pin "2") (pinfunction "2_2") (pintype "passive"))
      (node (ref "C2") (pin "1") (pinfunction "1_1") (pintype "passive"))
      (node (ref "C43") (pin "1") (pinfunction "1_1") (pintype "passive"))
      (node (ref "C44") (pin "1") (pinfunction "1_1") (pintype "passive"))
      (node (ref "C6") (pin "2") (pinfunction "2_2") (pintype "passive"))
      (node (ref "C7") (pin "2") (pinfunction "2_2") (pintype "passive"))
      (node (ref "C8") (pin "2") (pinfunction "2_2") (pintype "passive"))
      (node (ref "C9") (pin "2") (pinfunction "2_2") (pintype "passive"))
      (node (ref "D3") (pin "2") (pinfunction "K_2") (pintype "passive"))
      (node (ref "D5") (pin "2") (pinfunction "K_2") (pintype "passive"))
      (node (ref "L2") (pin "2") (pinfunction "2_2") (pintype "passive"))
      (node (ref "L3") (pin "1") (pinfunction "A_1") (pintype "passive"))
      (node (ref "P7") (pin "3") (pinfunction "3_3") (pintype "passive"))
      (node (ref "P7") (pin "4") (pinfunction "4_4") (pintype "passive"))
      (node (ref "U1") (pin "3") (pinfunction "FEEDBACK_3") (pintype "passive"))
      (node (ref "U10") (pin "13") (pinfunction "VCC_13") (pintype "passive"))
      (node (ref "U2") (pin "1") (pinfunction "EN_1") (pintype "passive"))
      (node (ref "U2") (pin "4") (pinfunction "VIN_4") (pintype "passive"))
      (node (ref "U6") (pin "3") (pinfunction "VCC_3") (pintype "passive"))
      (node (ref "U7") (pin "3") (pinfunction "VCC_3") (pintype "passive"))
    )
    (net (code "100") (name "GND") (class "Default")
      (node (ref "B1") (pin "2") (pinfunction "-_2") (pintype "passive"))
      (node (ref "C1") (pin "2") (pinfunction "2_2") (pintype "passive"))
      (node (ref "C10") (pin "1") (pinfunction "1_1") (pintype "passive"))
      (node (ref "C12") (pin "1") (pinfunction "1_1") (pintype "passive"))
      (node (ref "C13") (pin "1") (pinfunction "1_1") (pintype "passive"))
      (node (ref "C14") (pin "1") (pinfunction "1_1") (pintype "passive"))
      (node (ref "C15") (pin "1") (pinfunction "1_1") (pintype "passive"))
      (node (ref "C16") (pin "1") (pinfunction "1_1") (pintype "passive"))
      (node (ref "C17") (pin "1") (pinfunction "1_1") (pintype "passive"))
      (node (ref "C18") (pin "1") (pinfunction "1_1") (pintype "passive"))
      (node (ref "C19") (pin "1") (pinfunction "1_1") (pintype "passive"))
      (node (ref "C2") (pin "2") (pinfunction "2_2") (pintype "passive"))
      (node (ref "C20") (pin "1") (pinfunction "1_1") (pintype "passive"))
      (node (ref "C23") (pin "1") (pinfunction "1_1") (pintype "passive"))
      (node (ref "C25") (pin "1") (pinfunction "1_1") (pintype "passive"))
      (node (ref "C26") (pin "1") (pinfunction "1_1") (pintype "passive"))
      (node (ref "C27") (pin "1") (pinfunction "1_1") (pintype "passive"))
      (node (ref "C28") (pin "1") (pinfunction "1_1") (pintype "passive"))
      (node (ref "C29") (pin "2") (pinfunction "2_2") (pintype "passive"))
      (node (ref "C3") (pin "2") (pinfunction "2_2") (pintype "passive"))
      (node (ref "C30") (pin "2") (pinfunction "2_2") (pintype "passive"))
      (node (ref "C31") (pin "2") (pinfunction "2_2") (pintype "passive"))
      (node (ref "C32") (pin "2") (pinfunction "2_2") (pintype "passive"))
      (node (ref "C33") (pin "1") (pinfunction "1_1") (pintype "passive"))
      (node (ref "C34") (pin "1") (pinfunction "1_1") (pintype "passive"))
      (node (ref "C35") (pin "1") (pinfunction "1_1") (pintype "passive"))
      (node (ref "C36") (pin "1") (pinfunction "1_1") (pintype "passive"))
      (node (ref "C37") (pin "2") (pinfunction "2_2") (pintype "passive"))
      (node (ref "C38") (pin "2") (pinfunction "2_2") (pintype "passive"))
      (node (ref "C4") (pin "2") (pinfunction "2_2") (pintype "passive"))
      (node (ref "C40") (pin "1") (pinfunction "1_1") (pintype "passive"))
      (node (ref "C41") (pin "1") (pinfunction "1_1") (pintype "passive"))
      (node (ref "C42") (pin "1") (pinfunction "1_1") (pintype "passive"))
      (node (ref "C43") (pin "2") (pinfunction "2_2") (pintype "passive"))
      (node (ref "C44") (pin "2") (pinfunction "2_2") (pintype "passive"))
      (node (ref "C45") (pin "1") (pinfunction "1_1") (pintype "passive"))
      (node (ref "C46") (pin "1") (pinfunction "1_1") (pintype "passive"))
      (node (ref "C5") (pin "1") (pinfunction "1_1") (pintype "passive"))
      (node (ref "C6") (pin "1") (pinfunction "1_1") (pintype "passive"))
      (node (ref "C7") (pin "1") (pinfunction "1_1") (pintype "passive"))
      (node (ref "C8") (pin "1") (pinfunction "1_1") (pintype "passive"))
      (node (ref "C9") (pin "1") (pinfunction "1_1") (pintype "passive"))
      (node (ref "D10") (pin "1") (pinfunction "A_1") (pintype "passive"))
      (node (ref "D12") (pin "1") (pinfunction "A_1") (pintype "passive"))
      (node (ref "D13") (pin "1") (pinfunction "A_1") (pintype "passive"))
      (node (ref "D14") (pin "1") (pinfunction "A_1") (pintype "passive"))
      (node (ref "D15") (pin "1") (pinfunction "A_1") (pintype "passive"))
      (node (ref "D16") (pin "1") (pinfunction "A_1") (pintype "passive"))
      (node (ref "D17") (pin "1") (pinfunction "A_1") (pintype "passive"))
      (node (ref "D2") (pin "1") (pinfunction "A_1") (pintype "passive"))
      (node (ref "D3") (pin "1") (pinfunction "A_1") (pintype "passive"))
      (node (ref "D4") (pin "1") (pinfunction "A_1") (pintype "passive"))
      (node (ref "D8") (pin "3") (pinfunction "A_3") (pintype "passive"))
      (node (ref "D9") (pin "1") (pinfunction "A_1") (pintype "passive"))
      (node (ref "P1") (pin "2") (pinfunction "2_2") (pintype "passive"))
      (node (ref "P2") (pin "2") (pinfunction "2_2") (pintype "passive"))
      (node (ref "P3") (pin "4") (pinfunction "GND_4") (pintype "passive"))
      (node (ref "P4") (pin "3") (pinfunction "3_3") (pintype "passive"))
      (node (ref "P5") (pin "3") (pinfunction "3_3") (pintype "passive"))
      (node (ref "P7") (pin "1") (pinfunction "1_1") (pintype "passive"))
      (node (ref "P7") (pin "2") (pinfunction "2_2") (pintype "passive"))
      (node (ref "P7") (pin "39") (pinfunction "39_39") (pintype "passive"))
      (node (ref "P7") (pin "40") (pinfunction "40_40") (pintype "passive"))
      (node (ref "P7") (pin "41") (pinfunction "41_41") (pintype "passive"))
      (node (ref "P7") (pin "42") (pinfunction "42_42") (pintype "passive"))
      (node (ref "P8") (pin "2") (pinfunction "2_2") (pintype "passive"))
      (node (ref "Q1") (pin "2") (pinfunction "S_2") (pintype "passive"))
      (node (ref "R10") (pin "1") (pinfunction "1_1") (pintype "passive"))
      (node (ref "R19") (pin "2") (pinfunction "2_2") (pintype "passive"))
      (node (ref "R2") (pin "1") (pinfunction "1_1") (pintype "passive"))
      (node (ref "R23") (pin "2") (pinfunction "2_2") (pintype "passive"))
      (node (ref "R24") (pin "2") (pinfunction "2_2") (pintype "passive"))
      (node (ref "R25") (pin "2") (pinfunction "2_2") (pintype "passive"))
      (node (ref "R26") (pin "1") (pinfunction "1_1") (pintype "passive"))
      (node (ref "R27") (pin "2") (pinfunction "2_2") (pintype "passive"))
      (node (ref "R4") (pin "1") (pinfunction "1_1") (pintype "passive"))
      (node (ref "R5") (pin "1") (pinfunction "1_1") (pintype "passive"))
      (node (ref "U1") (pin "4") (pinfunction "ON/OFF_4") (pintype "passive"))
      (node (ref "U1") (pin "5") (pinfunction "GND_5") (pintype "passive"))
      (node (ref "U1") (pin "6") (pinfunction "GND_6") (pintype "passive"))
      (node (ref "U1") (pin "7") (pinfunction "GND_7") (pintype "passive"))
      (node (ref "U1") (pin "8") (pinfunction "GND_8") (pintype "passive"))
      (node (ref "U10") (pin "1") (pinfunction "GND_1") (pintype "passive"))
      (node (ref "U10") (pin "14") (pinfunction "GND_14") (pintype "passive"))
      (node (ref "U10") (pin "16") (pinfunction "GND_16") (pintype "passive"))
      (node (ref "U10") (pin "17") (pinfunction "GND_17") (pintype "passive"))
      (node (ref "U10") (pin "18") (pinfunction "GND_18") (pintype "passive"))
      (node (ref "U10") (pin "19") (pinfunction "GND_19") (pintype "passive"))
      (node (ref "U11") (pin "4") (pinfunction "GND_4") (pintype "passive"))
      (node (ref "U2") (pin "2") (pinfunction "GND_2") (pintype "passive"))
      (node (ref "U3") (pin "107") (pinfunction "VSS_107") (pintype "power_in"))
      (node (ref "U3") (pin "120") (pinfunction "VSS_120") (pintype "power_in"))
      (node (ref "U3") (pin "130") (pinfunction "VSS_130") (pintype "power_in"))
      (node (ref "U3") (pin "16") (pinfunction "VSS_16") (pintype "power_in"))
      (node (ref "U3") (pin "31") (pinfunction "VSSA_31") (pintype "power_in"))
      (node (ref "U3") (pin "38") (pinfunction "VSS_38") (pintype "power_in"))
      (node (ref "U3") (pin "51") (pinfunction "VSS_51") (pintype "power_in"))
      (node (ref "U3") (pin "61") (pinfunction "VSS_61") (pintype "power_in"))
      (node (ref "U3") (pin "83") (pinfunction "VSS_83") (pintype "power_in"))
      (node (ref "U3") (pin "94") (pinfunction "VSS_94") (pintype "power_in"))
      (node (ref "U4") (pin "15") (pinfunction "GND_15") (pintype "passive"))
      (node (ref "U5") (pin "5") (pinfunction "GND_5") (pintype "passive"))
      (node (ref "U6") (pin "2") (pinfunction "GND_2") (pintype "passive"))
      (node (ref "U6") (pin "8") (pinfunction "S_8") (pintype "passive"))
      (node (ref "U7") (pin "2") (pinfunction "GND_2") (pintype "passive"))
      (node (ref "U7") (pin "8") (pinfunction "S_8") (pintype "passive"))
      (node (ref "U8") (pin "12") (pinfunction "GND_12") (pintype "passive"))
      (node (ref "U8") (pin "34") (pinfunction "GND_34") (pintype "passive"))
      (node (ref "U9") (pin "25") (pinfunction "GND_25") (pintype "passive"))
    )
    (net (code "101") (name "Net-(B1-+)") (class "Default")
      (node (ref "B1") (pin "1") (pinfunction "+_1") (pintype "passive"))
      (node (ref "C20") (pin "2") (pinfunction "2_2") (pintype "passive"))
      (node (ref "D6") (pin "1") (pinfunction "A_1") (pintype "passive"))
      (node (ref "D7") (pin "2") (pinfunction "K_2") (pintype "passive"))
    )
    (net (code "102") (name "Net-(C39-Pad1)") (class "Default")
      (node (ref "C39") (pin "1") (pinfunction "1_1") (pintype "passive"))
      (node (ref "R21") (pin "2") (pinfunction "2_2") (pintype "passive"))
      (node (ref "R22") (pin "1") (pinfunction "1_1") (pintype "passive"))
    )
    (net (code "103") (name "Net-(C45-Pad2)") (class "Default")
      (node (ref "C45") (pin "2") (pinfunction "2_2") (pintype "passive"))
      (node (ref "R11") (pin "2") (pinfunction "2_2") (pintype "passive"))
      (node (ref "R12") (pin "1") (pinfunction "1_1") (pintype "passive"))
    )
    (net (code "104") (name "Net-(C46-Pad2)") (class "Default")
      (node (ref "C46") (pin "2") (pinfunction "2_2") (pintype "passive"))
      (node (ref "R13") (pin "2") (pinfunction "2_2") (pintype "passive"))
      (node (ref "R14") (pin "1") (pinfunction "1_1") (pintype "passive"))
    )
    (net (code "105") (name "Net-(D1-A)") (class "Default")
      (node (ref "D1") (pin "1") (pinfunction "A_1") (pintype "passive"))
      (node (ref "F1") (pin "2") (pinfunction "2_2") (pintype "passive"))
    )
    (net (code "106") (name "Net-(D1-K)") (class "Default")
      (node (ref "C1") (pin "1") (pinfunction "1_1") (pintype "passive"))
      (node (ref "C5") (pin "2") (pinfunction "2_2") (pintype "passive"))
      (node (ref "D1") (pin "2") (pinfunction "K_2") (pintype "passive"))
      (node (ref "D2") (pin "2") (pinfunction "K_2") (pintype "passive"))
      (node (ref "U1") (pin "1") (pinfunction "VIN_1") (pintype "passive"))
    )
    (net (code "107") (name "Net-(D4-K)") (class "Default")
      (node (ref "D4") (pin "2") (pinfunction "K_2") (pintype "passive"))
      (node (ref "L2") (pin "1") (pinfunction "1_1") (pintype "passive"))
      (node (ref "U1") (pin "2") (pinfunction "OUTPUT_2") (pintype "passive"))
    )
    (net (code "108") (name "Net-(D7-A)") (class "Default")
      (node (ref "D7") (pin "1") (pinfunction "A_1") (pintype "passive"))
      (node (ref "R3") (pin "1") (pinfunction "1_1") (pintype "passive"))
    )
    (net (code "109") (name "Net-(D11-K)") (class "Default")
      (node (ref "D11") (pin "2") (pinfunction "K_2") (pintype "passive"))
      (node (ref "R6") (pin "1") (pinfunction "1_1") (pintype "passive"))
    )
    (net (code "110") (name "Net-(D19-A)") (class "Default")
      (node (ref "D19") (pin "1") (pinfunction "A_1") (pintype "passive"))
      (node (ref "D5") (pin "1") (pinfunction "A_1") (pintype "passive"))
      (node (ref "P3") (pin "1") (pinfunction "5V_1") (pintype "passive"))
    )
    (net (code "111") (name "Net-(D19-K)") (class "Default")
      (node (ref "D19") (pin "2") (pinfunction "K_2") (pintype "passive"))
      (node (ref "R28") (pin "1") (pinfunction "1_1") (pintype "passive"))
    )
    (net (code "112") (name "Net-(F1-Pad1)") (class "Default")
      (node (ref "F1") (pin "1") (pinfunction "1_1") (pintype "passive"))
      (node (ref "P1") (pin "1") (pinfunction "1_1") (pintype "passive"))
      (node (ref "P2") (pin "1") (pinfunction "1_1") (pintype "passive"))
    )
    (net (code "113") (name "Net-(L3-B)") (class "Default")
      (node (ref "L3") (pin "2") (pinfunction "B_2") (pintype "passive"))
      (node (ref "Q1") (pin "3") (pinfunction "D_3") (pintype "passive"))
    )
    (net (code "114") (name "Net-(P3-D+)") (class "Default")
      (node (ref "D8") (pin "1") (pinfunction "K_1") (pintype "passive"))
      (node (ref "P3") (pin "3") (pinfunction "D+_3") (pintype "passive"))
      (node (ref "U3") (pin "104") (pinfunction "PA12/USART1_RTS/CAN1_TX/TIM1_ETR/OTG_FS_DP/EVENTOUT_104") (pintype "bidirectional"))
    )
    (net (code "115") (name "Net-(P3-D-)") (class "Default")
      (node (ref "D8") (pin "2") (pinfunction "K_2") (pintype "passive"))
      (node (ref "P3") (pin "2") (pinfunction "D-_2") (pintype "passive"))
      (node (ref "U3") (pin "103") (pinfunction "PA11/USART1_CTS/CAN1_RX/TIM1_CH4/OTG_FS_DM/EVENTOUT_103") (pintype "bidirectional"))
    )
    (net (code "116") (name "Net-(P6-RD+)") (class "Default")
      (node (ref "D18") (pin "3") (pinfunction "3_3") (pintype "passive"))
      (node (ref "D18") (pin "6") (pinfunction "6_6") (pintype "passive"))
      (node (ref "P6") (pin "3") (pinfunction "RD+_3") (pintype "passive"))
      (node (ref "T1") (pin "11") (pinfunction "11_11") (pintype "passive"))
    )
    (net (code "117") (name "Net-(P6-RD-)") (class "Default")
      (node (ref "D18") (pin "4") (pinfunction "4_4") (pintype "passive"))
      (node (ref "D18") (pin "5") (pinfunction "5_5") (pintype "passive"))
      (node (ref "P6") (pin "6") (pinfunction "RD-_6") (pintype "passive"))
      (node (ref "T1") (pin "9") (pinfunction "9_9") (pintype "passive"))
    )
    (net (code "118") (name "Net-(P6-TD+)") (class "Default")
      (node (ref "D18") (pin "1") (pinfunction "1_1") (pintype "passive"))
      (node (ref "D18") (pin "8") (pinfunction "8_8") (pintype "passive"))
      (node (ref "P6") (pin "1") (pinfunction "TD+_1") (pintype "passive"))
      (node (ref "T1") (pin "16") (pinfunction "16_16") (pintype "passive"))
    )
    (net (code "119") (name "Net-(P6-TD-)") (class "Default")
      (node (ref "D18") (pin "2") (pinfunction "2_2") (pintype "passive"))
      (node (ref "D18") (pin "7") (pinfunction "7_7") (pintype "passive"))
      (node (ref "P6") (pin "2") (pinfunction "TD-_2") (pintype "passive"))
      (node (ref "T1") (pin "14") (pinfunction "14_14") (pintype "passive"))
    )
    (net (code "120") (name "Net-(P6-绿LED+)") (class "Default")
      (node (ref "P6") (pin "11") (pinfunction "绿LED+_11") (pintype "passive"))
      (node (ref "R25") (pin "1") (pinfunction "1_1") (pintype "passive"))
      (node (ref "U9") (pin "3") (pinfunction "LED1/~{REGOFF}_3") (pintype "passive"))
    )
    (net (code "121") (name "Net-(P6-绿LED-)") (class "Default")
      (node (ref "P6") (pin "12") (pinfunction "绿LED-_12") (pintype "passive"))
      (node (ref "R26") (pin "2") (pinfunction "2_2") (pintype "passive"))
    )
    (net (code "122") (name "Net-(P6-黄LED+)") (class "Default")
      (node (ref "P6") (pin "9") (pinfunction "黄LED+_9") (pintype "passive"))
      (node (ref "R24") (pin "1") (pinfunction "1_1") (pintype "passive"))
      (node (ref "U9") (pin "2") (pinfunction "LED2/~{nNTSEL}_2") (pintype "passive"))
    )
    (net (code "123") (name "Net-(P6-黄LED-)") (class "Default")
      (node (ref "P6") (pin "10") (pinfunction "黄LED-_10") (pintype "passive"))
      (node (ref "R27") (pin "1") (pinfunction "1_1") (pintype "passive"))
    )
    (net (code "124") (name "Net-(Q1-G)") (class "Default")
      (node (ref "Q1") (pin "1") (pinfunction "G_1") (pintype "passive"))
      (node (ref "U3") (pin "37") (pinfunction "PA3/USART2_RX/TIM5_CH4/TIM9_CH2/TIM2_CH4/OTG_HS_ULPI_D0/ETH_MII_COL/EVENTOUT/ADC123_IN3_37") (pintype "bidirectional"))
    )
    (net (code "125") (name "Net-(R21-Pad1)") (class "Default")
      (node (ref "R21") (pin "1") (pinfunction "1_1") (pintype "passive"))
      (node (ref "T1") (pin "10") (pinfunction "10_10") (pintype "passive"))
    )
    (net (code "126") (name "Net-(R22-Pad2)") (class "Default")
      (node (ref "R22") (pin "2") (pinfunction "2_2") (pintype "passive"))
      (node (ref "T1") (pin "15") (pinfunction "15_15") (pintype "passive"))
    )
    (net (code "127") (name "Net-(U2-SW)") (class "Default")
      (node (ref "L1") (pin "1") (pinfunction "1_1") (pintype "passive"))
      (node (ref "U2") (pin "3") (pinfunction "SW_3") (pintype "passive"))
    )
    (net (code "128") (name "Net-(U2-VOUT{slash}FB)") (class "Default")
      (node (ref "C11") (pin "1") (pinfunction "1_1") (pintype "passive"))
      (node (ref "R1") (pin "1") (pinfunction "1_1") (pintype "passive"))
      (node (ref "R2") (pin "2") (pinfunction "2_2") (pintype "passive"))
      (node (ref "U2") (pin "5") (pinfunction "VOUT/FB_5") (pintype "passive"))
    )
    (net (code "129") (name "Net-(U3-PA9{slash}USART1_TX{slash}TIM1_CH2{slash}I2C3_SMBA{slash}DCMI_D0{slash}EVENTOUT{slash}OTG_FS_VBUS)") (class "Default")
      (node (ref "R28") (pin "2") (pinfunction "2_2") (pintype "passive"))
      (node (ref "U3") (pin "101") (pinfunction "PA9/USART1_TX/TIM1_CH2/I2C3_SMBA/DCMI_D0/EVENTOUT/OTG_FS_VBUS_101") (pintype "bidirectional"))
    )
    (net (code "130") (name "Net-(U3-PC14-OSC32_IN(PC14){slash}EVENTOUT{slash}OSC32_IN)") (class "Default")
      (node (ref "C31") (pin "1") (pinfunction "1_1") (pintype "passive"))
      (node (ref "U3") (pin "8") (pinfunction "PC14-OSC32_IN(PC14)/EVENTOUT/OSC32_IN_8") (pintype "bidirectional"))
      (node (ref "Y2") (pin "2") (pinfunction "OSC2_2") (pintype "passive"))
    )
    (net (code "131") (name "Net-(U3-PC15-OSC32_OUT(PC15){slash}EVENTOUT{slash}OSC32_OUT)") (class "Default")
      (node (ref "C32") (pin "1") (pinfunction "1_1") (pintype "passive"))
      (node (ref "U3") (pin "9") (pinfunction "PC15-OSC32_OUT(PC15)/EVENTOUT/OSC32_OUT_9") (pintype "bidirectional"))
      (node (ref "Y2") (pin "1") (pinfunction "OSC1_1") (pintype "passive"))
    )
    (net (code "132") (name "Net-(U3-PH0-OSC_IN(PH0){slash}EVENTOUT{slash}OSC_IN)") (class "Default")
      (node (ref "C29") (pin "1") (pinfunction "1_1") (pintype "passive"))
      (node (ref "U3") (pin "23") (pinfunction "PH0-OSC_IN(PH0)/EVENTOUT/OSC_IN_23") (pintype "bidirectional"))
      (node (ref "Y1") (pin "2") (pinfunction "OSC2_2") (pintype "passive"))
    )
    (net (code "133") (name "Net-(U3-PH1-OSC_OUT(PH1){slash}EVENTOUT{slash}OSC_OUT)") (class "Default")
      (node (ref "C30") (pin "1") (pinfunction "1_1") (pintype "passive"))
      (node (ref "U3") (pin "24") (pinfunction "PH1-OSC_OUT(PH1)/EVENTOUT/OSC_OUT_24") (pintype "bidirectional"))
      (node (ref "Y1") (pin "1") (pinfunction "OSC1_1") (pintype "passive"))
    )
    (net (code "134") (name "Net-(U3-VCAP_1)") (class "Default")
      (node (ref "C26") (pin "2") (pinfunction "2_2") (pintype "passive"))
      (node (ref "U3") (pin "71") (pinfunction "VCAP_1_71") (pintype "power_in"))
    )
    (net (code "135") (name "Net-(U3-VCAP_2)") (class "Default")
      (node (ref "C27") (pin "2") (pinfunction "2_2") (pintype "passive"))
      (node (ref "U3") (pin "106") (pinfunction "VCAP_2_106") (pintype "power_in"))
    )
    (net (code "136") (name "Net-(U4-C1+)") (class "Default")
      (node (ref "C21") (pin "2") (pinfunction "2_2") (pintype "passive"))
      (node (ref "U4") (pin "1") (pinfunction "C1+_1") (pintype "passive"))
    )
    (net (code "137") (name "Net-(U4-C1-)") (class "Default")
      (node (ref "C21") (pin "1") (pinfunction "1_1") (pintype "passive"))
      (node (ref "U4") (pin "3") (pinfunction "C1-_3") (pintype "passive"))
    )
    (net (code "138") (name "Net-(U4-C2+)") (class "Default")
      (node (ref "C24") (pin "2") (pinfunction "2_2") (pintype "passive"))
      (node (ref "U4") (pin "4") (pinfunction "C2+_4") (pintype "passive"))
    )
    (net (code "139") (name "Net-(U4-C2-)") (class "Default")
      (node (ref "C24") (pin "1") (pinfunction "1_1") (pintype "passive"))
      (node (ref "U4") (pin "5") (pinfunction "C2-_5") (pintype "passive"))
    )
    (net (code "140") (name "Net-(U4-V+)") (class "Default")
      (node (ref "C22") (pin "1") (pinfunction "1_1") (pintype "passive"))
      (node (ref "U4") (pin "2") (pinfunction "V+_2") (pintype "passive"))
    )
    (net (code "141") (name "Net-(U4-V-)") (class "Default")
      (node (ref "C25") (pin "2") (pinfunction "2_2") (pintype "passive"))
      (node (ref "U4") (pin "6") (pinfunction "V-_6") (pintype "passive"))
    )
    (net (code "142") (name "Net-(U5-A)") (class "Default")
      (node (ref "R7") (pin "2") (pinfunction "2_2") (pintype "passive"))
      (node (ref "U5") (pin "6") (pinfunction "A_6") (pintype "passive"))
    )
    (net (code "143") (name "Net-(U5-B)") (class "Default")
      (node (ref "R9") (pin "2") (pinfunction "2_2") (pintype "passive"))
      (node (ref "U5") (pin "7") (pinfunction "B_7") (pintype "passive"))
    )
    (net (code "144") (name "Net-(U9-RBIAS)") (class "Default")
      (node (ref "R23") (pin "1") (pinfunction "1_1") (pintype "passive"))
      (node (ref "U9") (pin "24") (pinfunction "RBIAS_24") (pintype "passive"))
    )
    (net (code "145") (name "Net-(U9-RXER{slash}~{PHYAD0})") (class "Default")
      (node (ref "R19") (pin "1") (pinfunction "1_1") (pintype "passive"))
      (node (ref "U9") (pin "10") (pinfunction "RXER/~{PHYAD0}_10") (pintype "passive"))
    )
    (net (code "146") (name "Net-(U9-RXN)") (class "Default")
      (node (ref "R15") (pin "1") (pinfunction "1_1") (pintype "passive"))
      (node (ref "T1") (pin "8") (pinfunction "8_8") (pintype "passive"))
      (node (ref "U9") (pin "22") (pinfunction "RXN_22") (pintype "passive"))
    )
    (net (code "147") (name "Net-(U9-RXP)") (class "Default")
      (node (ref "R16") (pin "1") (pinfunction "1_1") (pintype "passive"))
      (node (ref "T1") (pin "6") (pinfunction "6_6") (pintype "passive"))
      (node (ref "U9") (pin "23") (pinfunction "RXP_23") (pintype "passive"))
    )
    (net (code "148") (name "Net-(U9-TXN)") (class "Default")
      (node (ref "R17") (pin "1") (pinfunction "1_1") (pintype "passive"))
      (node (ref "T1") (pin "3") (pinfunction "3_3") (pintype "passive"))
      (node (ref "U9") (pin "20") (pinfunction "TXN_20") (pintype "passive"))
    )
    (net (code "149") (name "Net-(U9-TXP)") (class "Default")
      (node (ref "R18") (pin "1") (pinfunction "1_1") (pintype "passive"))
      (node (ref "T1") (pin "1") (pinfunction "1_1") (pintype "passive"))
      (node (ref "U9") (pin "21") (pinfunction "TXP_21") (pintype "passive"))
    )
    (net (code "150") (name "Net-(U9-VDD1A)") (class "Default")
      (node (ref "C34") (pin "2") (pinfunction "2_2") (pintype "passive"))
      (node (ref "C35") (pin "2") (pinfunction "2_2") (pintype "passive"))
      (node (ref "I1") (pin "1") (pinfunction "1_1") (pintype "passive"))
      (node (ref "R15") (pin "2") (pinfunction "2_2") (pintype "passive"))
      (node (ref "R16") (pin "2") (pinfunction "2_2") (pintype "passive"))
      (node (ref "R17") (pin "2") (pinfunction "2_2") (pintype "passive"))
      (node (ref "R18") (pin "2") (pinfunction "2_2") (pintype "passive"))
      (node (ref "T1") (pin "2") (pinfunction "2_2") (pintype "passive"))
      (node (ref "T1") (pin "7") (pinfunction "7_7") (pintype "passive"))
      (node (ref "U9") (pin "1") (pinfunction "VDD2A_1") (pintype "passive"))
      (node (ref "U9") (pin "19") (pinfunction "VDD1A_19") (pintype "passive"))
    )
    (net (code "151") (name "Net-(U9-XTAL1{slash}CLKIN)") (class "Default")
      (node (ref "C37") (pin "1") (pinfunction "1_1") (pintype "passive"))
      (node (ref "U9") (pin "5") (pinfunction "XTAL1/CLKIN_5") (pintype "passive"))
      (node (ref "Y3") (pin "2") (pinfunction "OSC2_2") (pintype "passive"))
    )
    (net (code "152") (name "Net-(U9-XTAL2)") (class "Default")
      (node (ref "C38") (pin "1") (pinfunction "1_1") (pintype "passive"))
      (node (ref "U9") (pin "4") (pinfunction "XTAL2_4") (pintype "passive"))
      (node (ref "Y3") (pin "1") (pinfunction "OSC1_1") (pintype "passive"))
    )
    (net (code "153") (name "Net-(U9-nRST)") (class "Default")
      (node (ref "R20") (pin "1") (pinfunction "1_1") (pintype "passive"))
      (node (ref "U9") (pin "15") (pinfunction "nRST_15") (pintype "passive"))
    )
    (net (code "154") (name "Net-(U10-ANT)") (class "Default")
      (node (ref "P8") (pin "1") (pinfunction "1_1") (pintype "passive"))
      (node (ref "U10") (pin "20") (pinfunction "ANT_20") (pintype "passive"))
    )
    (net (code "155") (name "PE") (class "Default")
      (node (ref "C39") (pin "2") (pinfunction "2_2") (pintype "passive"))
      (node (ref "P6") (pin "13") (pinfunction "NC_13") (pintype "passive"))
      (node (ref "P6") (pin "14") (pinfunction "NC_14") (pintype "passive"))
    )
    (net (code "156") (name "unconnected-(P1-NC-Pad3)") (class "Default")
      (node (ref "P1") (pin "3") (pinfunction "NC_3") (pintype "passive+no_connect"))
    )
    (net (code "157") (name "unconnected-(P3-NC-Pad5)") (class "Default")
      (node (ref "P3") (pin "5") (pinfunction "NC_5") (pintype "passive+no_connect"))
    )
    (net (code "158") (name "unconnected-(P6-Pad4)") (class "Default")
      (node (ref "P6") (pin "4") (pintype "passive+no_connect"))
    )
    (net (code "159") (name "unconnected-(P6-Pad5)") (class "Default")
      (node (ref "P6") (pin "5") (pintype "passive+no_connect"))
    )
    (net (code "160") (name "unconnected-(P6-Pad7)") (class "Default")
      (node (ref "P6") (pin "7") (pintype "passive+no_connect"))
    )
    (net (code "161") (name "unconnected-(P6-Pad8)") (class "Default")
      (node (ref "P6") (pin "8") (pintype "passive+no_connect"))
    )
    (net (code "162") (name "unconnected-(U3-PA0-WKUP(PA0){slash}USART2_CTS{slash}UART4_TX{slash}ETH_MII_CRS{slash}TIM2_CH1_ETR{slash}TIM5_CH1{slash}TIM8_ETR{slash}EVENTOUT{slash}ADC123_IN0{slash}WKUP-Pad34)") (class "Default")
      (node (ref "U3") (pin "34") (pinfunction "PA0-WKUP(PA0)/USART2_CTS/UART4_TX/ETH_MII_CRS/TIM2_CH1_ETR/TIM5_CH1/TIM8_ETR/EVENTOUT/ADC123_IN0/WKUP_34") (pintype "bidirectional+no_connect"))
    )
    (net (code "163") (name "unconnected-(U3-PA4{slash}SPI1_NSS{slash}SPI3_NSS{slash}USART2_CK{slash}DCMI_HSYNC{slash}OTG_HS_SOF{slash}I2S3_WS{slash}EVENTOUT{slash}ADC12_IN4{slash}DAC1_OUT-Pad40)") (class "Default")
      (node (ref "U3") (pin "40") (pinfunction "PA4/SPI1_NSS/SPI3_NSS/USART2_CK/DCMI_HSYNC/OTG_HS_SOF/I2S3_WS/EVENTOUT/ADC12_IN4/DAC1_OUT_40") (pintype "bidirectional+no_connect"))
    )
    (net (code "164") (name "unconnected-(U3-PA5{slash}SPI1_SCK{slash}OTG_HS_ULPI_CK{slash}TIM2_CH1_ETR{slash}TIM8_CHIN{slash}EVENTOUT{slash}ADC12_IN5{slash}DAC2_OUT-Pad41)") (class "Default")
      (node (ref "U3") (pin "41") (pinfunction "PA5/SPI1_SCK/OTG_HS_ULPI_CK/TIM2_CH1_ETR/TIM8_CHIN/EVENTOUT/ADC12_IN5/DAC2_OUT_41") (pintype "bidirectional+no_connect"))
    )
    (net (code "165") (name "unconnected-(U3-PA6{slash}SPI1_MISO{slash}TIM8_BKIN{slash}TIM13_CH1{slash}DCMI_PIXCLK{slash}TIM3_CH1{slash}TIM1_BKIN{slash}EVENTOUT{slash}ADC12_IN6-Pad42)") (class "Default")
      (node (ref "U3") (pin "42") (pinfunction "PA6/SPI1_MISO/TIM8_BKIN/TIM13_CH1/DCMI_PIXCLK/TIM3_CH1/TIM1_BKIN/EVENTOUT/ADC12_IN6_42") (pintype "bidirectional+no_connect"))
    )
    (net (code "166") (name "unconnected-(U3-PB0{slash}TIM3_CH3{slash}TIM8_CH2N{slash}OTG_HS_ULPI_D1{slash}ETH_MII_RXD2{slash}TIM1_CH2N{slash}EVENTOUT{slash}ADC12_IN8-Pad46)") (class "Default")
      (node (ref "U3") (pin "46") (pinfunction "PB0/TIM3_CH3/TIM8_CH2N/OTG_HS_ULPI_D1/ETH_MII_RXD2/TIM1_CH2N/EVENTOUT/ADC12_IN8_46") (pintype "bidirectional+no_connect"))
    )
    (net (code "167") (name "unconnected-(U3-PB1{slash}TIM3_CH4{slash}TIM8_CH3N{slash}OTG_HS_ULPI_D2{slash}ETH_MII_RXD3{slash}OTG_HS_INTN{slash}TIM1_CH3N{slash}EVENTOUT{slash}ADC12_IN9-Pad47)") (class "Default")
      (node (ref "U3") (pin "47") (pinfunction "PB1/TIM3_CH4/TIM8_CH3N/OTG_HS_ULPI_D2/ETH_MII_RXD3/OTG_HS_INTN/TIM1_CH3N/EVENTOUT/ADC12_IN9_47") (pintype "bidirectional+no_connect"))
    )
    (net (code "168") (name "unconnected-(U3-PB14{slash}SPI2_MISO{slash}TIM1_CH2N{slash}TIM12_CH1{slash}OTG_HS_DM{slash}USART3_RTS{slash}TIM8_CH2N{slash}I2S2ext_SD{slash}EVENTOUT-Pad75)") (class "Default")
      (node (ref "U3") (pin "75") (pinfunction "PB14/SPI2_MISO/TIM1_CH2N/TIM12_CH1/OTG_HS_DM/USART3_RTS/TIM8_CH2N/I2S2ext_SD/EVENTOUT_75") (pintype "bidirectional+no_connect"))
    )
    (net (code "169") (name "unconnected-(U3-PB15{slash}SPI2_MOSI{slash}I2S2_SD{slash}TIM1_CH3N{slash}TIM8_CH3N{slash}TIM12_CH2{slash}OTG_HS_DP{slash}EVENTOUT-Pad76)") (class "Default")
      (node (ref "U3") (pin "76") (pinfunction "PB15/SPI2_MOSI/I2S2_SD/TIM1_CH3N/TIM8_CH3N/TIM12_CH2/OTG_HS_DP/EVENTOUT_76") (pintype "bidirectional+no_connect"))
    )
    (net (code "170") (name "unconnected-(U3-PC0{slash}OTG_HS_ULPI_STP{slash}EVENTOUT{slash}ADC123_IN10-Pad26)") (class "Default")
      (node (ref "U3") (pin "26") (pinfunction "PC0/OTG_HS_ULPI_STP/EVENTOUT/ADC123_IN10_26") (pintype "bidirectional+no_connect"))
    )
    (net (code "171") (name "unconnected-(U3-PC2{slash}SPI2_MISO{slash}OTG_HS_ULPI_DIR{slash}TH_MII_TXD2{slash}I2S2ext_SD{slash}EVENTOUT{slash}ADC123_IN12-Pad28)") (class "Default")
      (node (ref "U3") (pin "28") (pinfunction "PC2/SPI2_MISO/OTG_HS_ULPI_DIR/TH_MII_TXD2/I2S2ext_SD/EVENTOUT/ADC123_IN12_28") (pintype "bidirectional+no_connect"))
    )
    (net (code "172") (name "unconnected-(U3-PC3{slash}SPI2_MOSI{slash}I2S2_SD{slash}OTG_HS_ULPI_NXT{slash}ETH_MII_TX_CLK{slash}EVENTOUT{slash}ADC123_IN13-Pad29)") (class "Default")
      (node (ref "U3") (pin "29") (pinfunction "PC3/SPI2_MOSI/I2S2_SD/OTG_HS_ULPI_NXT/ETH_MII_TX_CLK/EVENTOUT/ADC123_IN13_29") (pintype "bidirectional+no_connect"))
    )
    (net (code "173") (name "unconnected-(U3-PD6{slash}FSMC_NWAIT{slash}USART2_RX{slash}EVENTOUT-Pad122)") (class "Default")
      (node (ref "U3") (pin "122") (pinfunction "PD6/FSMC_NWAIT/USART2_RX/EVENTOUT_122") (pintype "bidirectional+no_connect"))
    )
    (net (code "174") (name "unconnected-(U3-PE3{slash}TRACED0{slash}FSMC_A19{slash}EVENTOUT-Pad2)") (class "Default")
      (node (ref "U3") (pin "2") (pinfunction "PE3/TRACED0/FSMC_A19/EVENTOUT_2") (pintype "bidirectional+no_connect"))
    )
    (net (code "175") (name "unconnected-(U3-PF7{slash}TIM11_CH1{slash}FSMC_NREG{slash}EVENTOUT{slash}ADC3_IN5-Pad19)") (class "Default")
      (node (ref "U3") (pin "19") (pinfunction "PF7/TIM11_CH1/FSMC_NREG/EVENTOUT/ADC3_IN5_19") (pintype "bidirectional+no_connect"))
    )
    (net (code "176") (name "unconnected-(U3-PF8{slash}TIM13_CH1{slash}FSMC_NIOWR{slash}EVENTOUT{slash}ADC3_IN6-Pad20)") (class "Default")
      (node (ref "U3") (pin "20") (pinfunction "PF8/TIM13_CH1/FSMC_NIOWR/EVENTOUT/ADC3_IN6_20") (pintype "bidirectional+no_connect"))
    )
    (net (code "177") (name "unconnected-(U3-PF9{slash}TIM14_CH1{slash}FSMC_CD{slash}EVENTOUT{slash}ADC3_IN7-Pad21)") (class "Default")
      (node (ref "U3") (pin "21") (pinfunction "PF9/TIM14_CH1/FSMC_CD/EVENTOUT/ADC3_IN7_21") (pintype "bidirectional+no_connect"))
    )
    (net (code "178") (name "unconnected-(U3-PF10{slash}FSMC_INTR{slash}EVENTOUT{slash}ADC3_IN8-Pad22)") (class "Default")
      (node (ref "U3") (pin "22") (pinfunction "PF10/FSMC_INTR/EVENTOUT/ADC3_IN8_22") (pintype "bidirectional+no_connect"))
    )
    (net (code "179") (name "unconnected-(U3-PG6{slash}FSMC_INT2{slash}EVENTOUT-Pad91)") (class "Default")
      (node (ref "U3") (pin "91") (pinfunction "PG6/FSMC_INT2/EVENTOUT_91") (pintype "bidirectional+no_connect"))
    )
    (net (code "180") (name "unconnected-(U3-PG7{slash}FSMC_INT3{slash}USART6_CK{slash}EVENTOUT-Pad92)") (class "Default")
      (node (ref "U3") (pin "92") (pinfunction "PG7/FSMC_INT3/USART6_CK/EVENTOUT_92") (pintype "bidirectional+no_connect"))
    )
    (net (code "181") (name "unconnected-(U3-PG8{slash}USART6_RTS{slash}ETH_PPS_OUT{slash}EVENTOUT-Pad93)") (class "Default")
      (node (ref "U3") (pin "93") (pinfunction "PG8/USART6_RTS/ETH_PPS_OUT/EVENTOUT_93") (pintype "bidirectional+no_connect"))
    )
    (net (code "182") (name "unconnected-(U3-PG9{slash}USART6_RX{slash}FSMC_NE2{slash}FSMC_NCE3{slash}EVENTOUT-Pad124)") (class "Default")
      (node (ref "U3") (pin "124") (pinfunction "PG9/USART6_RX/FSMC_NE2/FSMC_NCE3/EVENTOUT_124") (pintype "bidirectional+no_connect"))
    )
    (net (code "183") (name "unconnected-(U4-R1IN-Pad13)") (class "Default")
      (node (ref "U4") (pin "13") (pinfunction "R1IN_13") (pintype "passive"))
    )
    (net (code "184") (name "unconnected-(U4-R1OUT-Pad12)") (class "Default")
      (node (ref "U4") (pin "12") (pinfunction "R1OUT_12") (pintype "passive"))
    )
    (net (code "185") (name "unconnected-(U4-T1IN-Pad11)") (class "Default")
      (node (ref "U4") (pin "11") (pinfunction "T1IN_11") (pintype "passive"))
    )
    (net (code "186") (name "unconnected-(U4-T1OUT-Pad14)") (class "Default")
      (node (ref "U4") (pin "14") (pinfunction "T1OUT_14") (pintype "passive"))
    )
    (net (code "187") (name "unconnected-(U10-GPIO0-Pad12)") (class "Default")
      (node (ref "U10") (pin "12") (pinfunction "GPIO0_12") (pintype "passive+no_connect"))
    )
    (net (code "188") (name "unconnected-(U10-GPIO1-Pad11)") (class "Default")
      (node (ref "U10") (pin "11") (pinfunction "GPIO1_11") (pintype "passive+no_connect"))
    )
    (net (code "189") (name "unconnected-(U10-GPIO2-Pad4)") (class "Default")
      (node (ref "U10") (pin "4") (pinfunction "GPIO2_4") (pintype "passive+no_connect"))
    )
    (net (code "190") (name "unconnected-(U10-GPIO3-Pad3)") (class "Default")
      (node (ref "U10") (pin "3") (pinfunction "GPIO3_3") (pintype "passive+no_connect"))
    )
  )
)
